# 8Port.net
KiCad netlist of a schematic drawn in Altium Designer
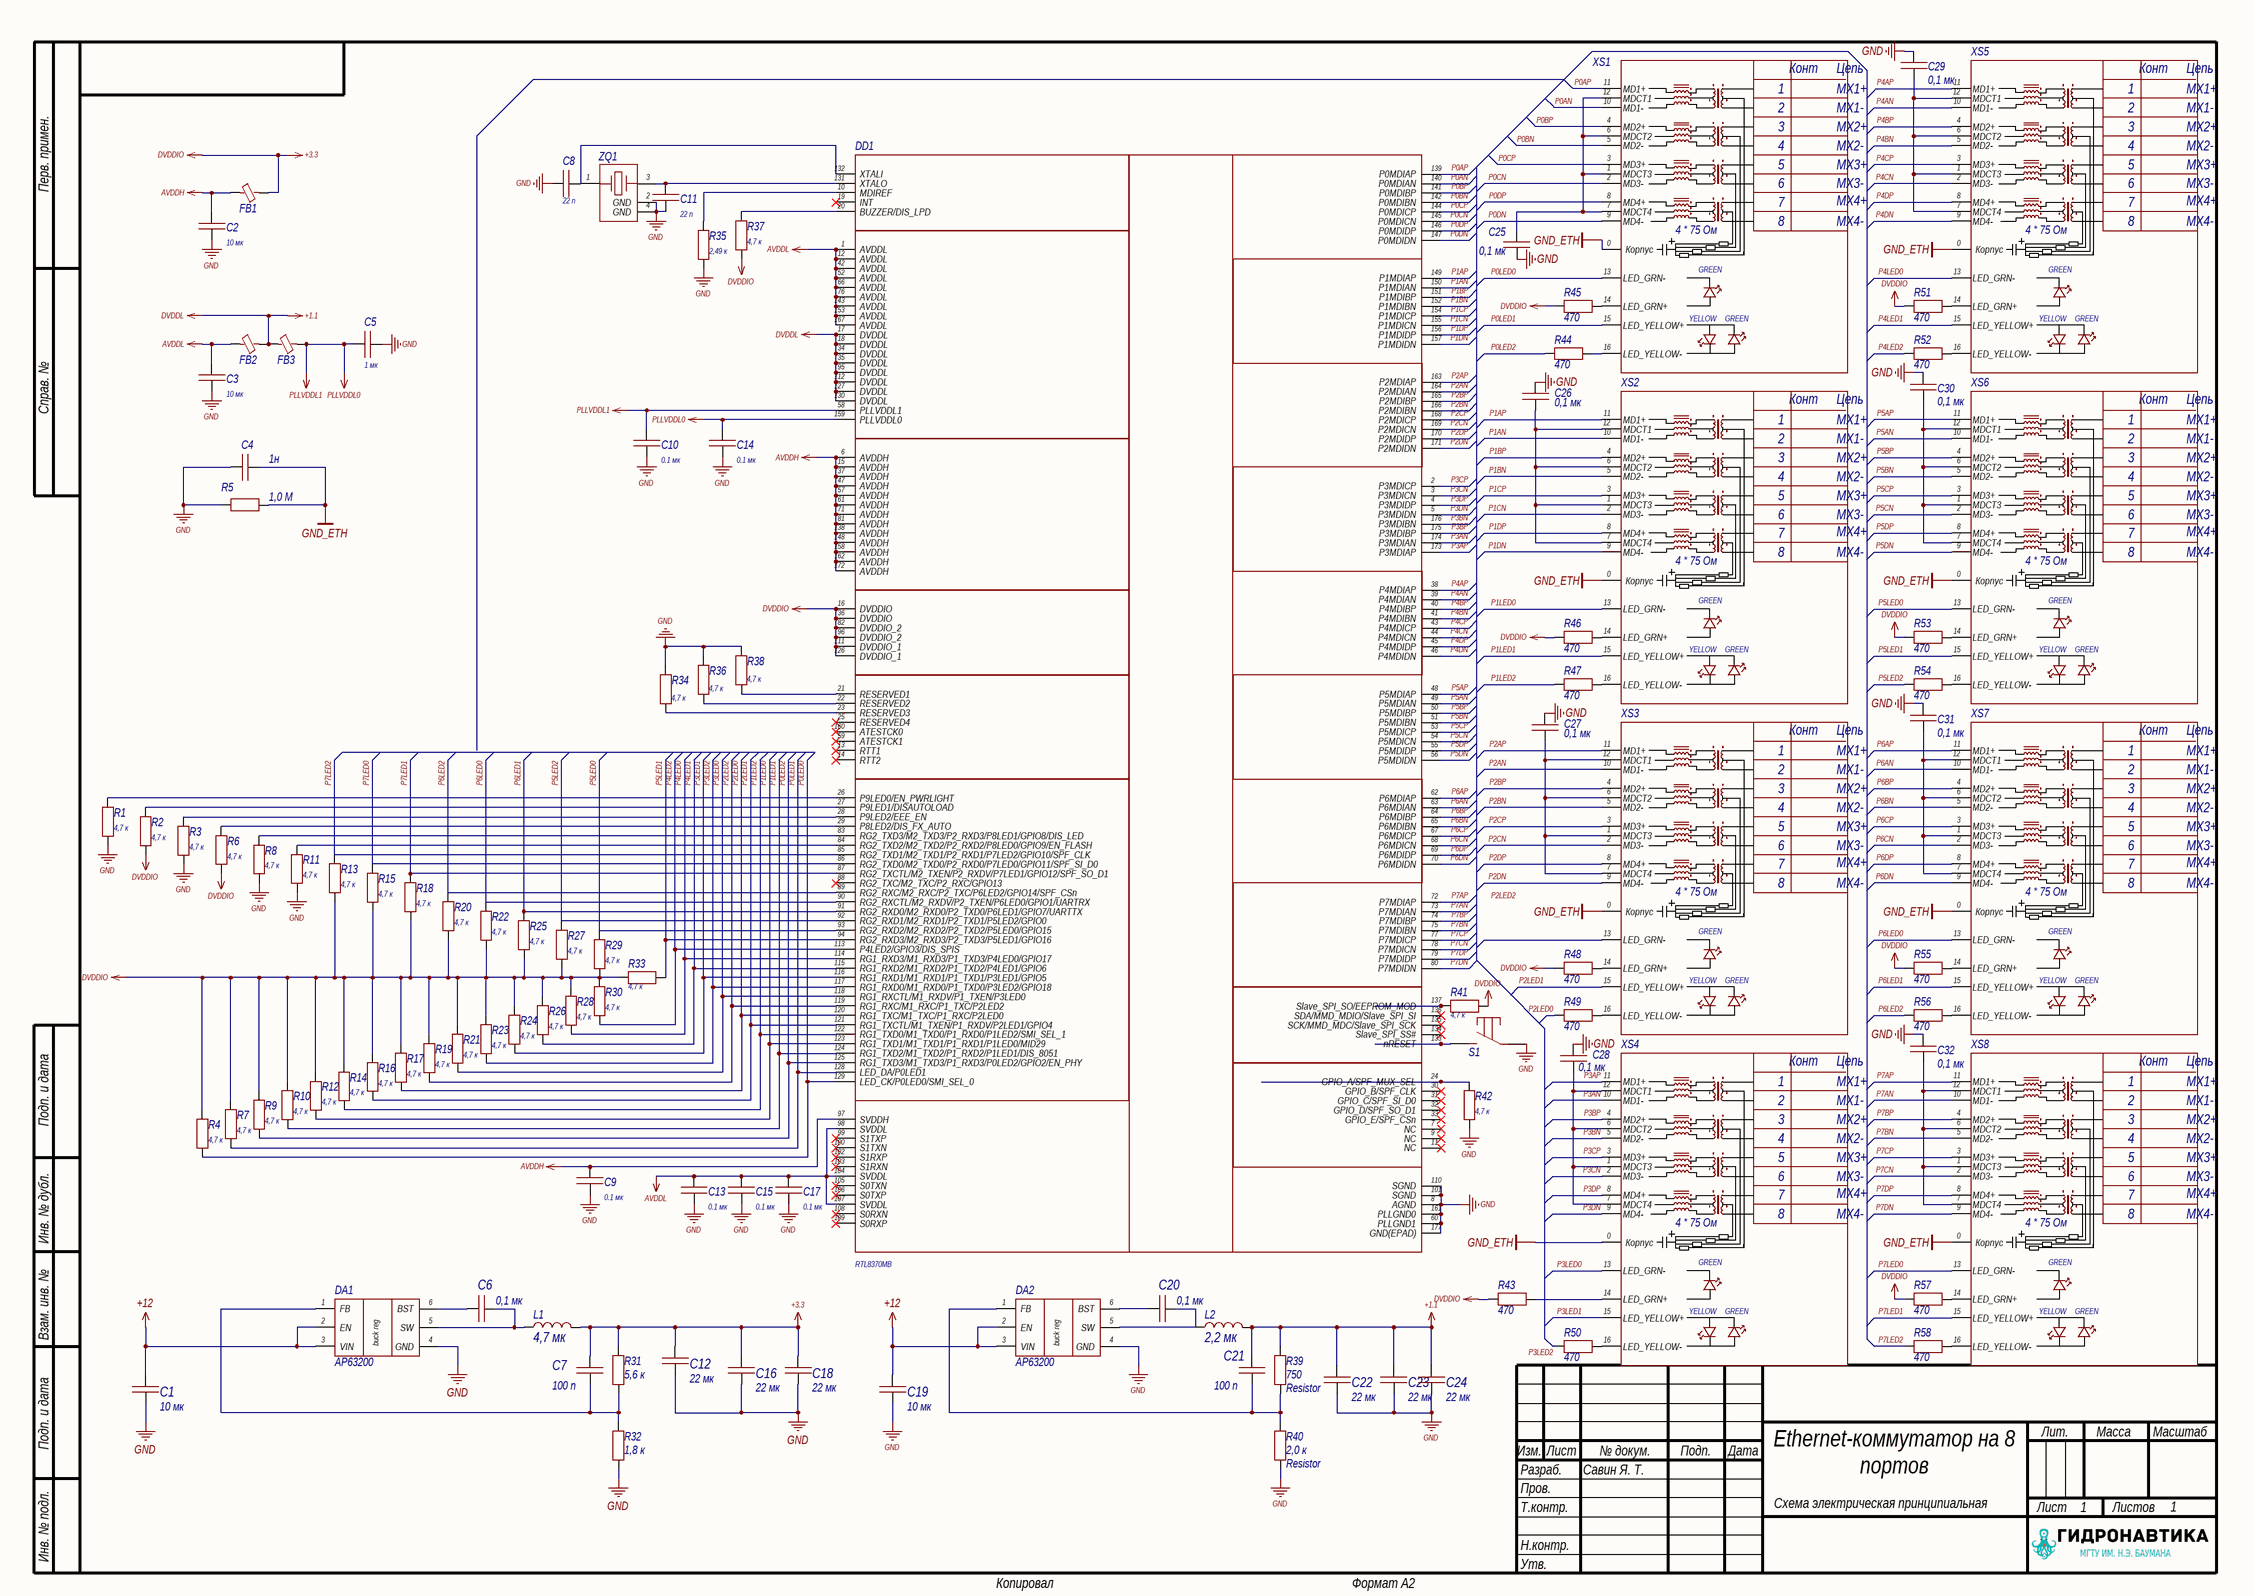
[diagram p0: 8Port.SchDoc]

(export (version "E")
  (design (tool "Eeschema 10.0.6"))
  (components
    (comp (ref "C1")
      (value "10 мк")
      (footprint "1210C")
      (description "Конденсатор 1210C ёмкостью 10 мк 10%, 35 В, X7R")
      (fields (field (name "PART NUMBER") "Capacitor_10u_10_35V_X7R_1210C") (field (name "TOLERANCE") "10%"))
      (libsource (lib "Hydrolib") (part "Capacitor"))
    )
    (comp (ref "C2")
      (value "10 мк")
      (footprint "0603C")
      (description "Конденсатор")
      (fields (field (name "PART NUMBER") "Capacitor"))
      (libsource (lib "Hydrolib") (part "Capacitor"))
    )
    (comp (ref "C3")
      (value "10 мк")
      (footprint "0603C")
      (description "Конденсатор")
      (fields (field (name "PART NUMBER") "Capacitor"))
      (libsource (lib "Hydrolib") (part "Capacitor"))
    )
    (comp (ref "C4")
      (value "1н")
      (footprint "1210C")
      (description "Конденсатор 1210C ёмкостью 1н 10%, 1000 В, X7R")
      (fields
        (field (name "PART NUMBER") "Capacitor_1n_10_1000V_X7R_1206C")
        (field (name "TOLERANCE") "10%")
        (field (name "АВТОР") "rreali")
      )
      (libsource (lib "Hydrolib") (part "Capacitor"))
    )
    (comp (ref "C5")
      (value "1 мк")
      (footprint "0603C")
      (description "Конденсатор")
      (fields (field (name "PART NUMBER") "Capacitor"))
      (libsource (lib "Hydrolib") (part "Capacitor"))
    )
    (comp (ref "C6")
      (value "0,1 мк")
      (footprint "0603C")
      (description "Конденсатор 0603C ёмкостью 0,1 мк 10%, 50 В, X7R")
      (fields (field (name "PART NUMBER") "Capacitor_0,1u_10_50V_X7R_0603C") (field (name "TOLERANCE") "10%"))
      (libsource (lib "Hydrolib") (part "Capacitor"))
    )
    (comp (ref "C7")
      (value "100 п")
      (footprint "0603C")
      (description "Конденсатор 0603C ёмкостью 100 п 10%, 50 В, X7R")
      (fields (field (name "PART NUMBER") "Capacitor_100p_10_50V_X7R_0603C") (field (name "TOLERANCE") "10%"))
      (libsource (lib "Hydrolib") (part "Capacitor"))
    )
    (comp (ref "C8")
      (value "22 п")
      (footprint "0603C")
      (description "Конденсатор")
      (fields (field (name "PART NUMBER") "Capacitor"))
      (libsource (lib "Hydrolib") (part "Capacitor"))
    )
    (comp (ref "C9")
      (value "0.1 мк")
      (footprint "0603C")
      (description "Конденсатор")
      (fields (field (name "PART NUMBER") "Capacitor"))
      (libsource (lib "Hydrolib") (part "Capacitor"))
    )
    (comp (ref "C10")
      (value "0.1 мк")
      (footprint "0603C")
      (description "Конденсатор")
      (fields (field (name "PART NUMBER") "Capacitor"))
      (libsource (lib "Hydrolib") (part "Capacitor"))
    )
    (comp (ref "C11")
      (value "22 п")
      (footprint "0603C")
      (description "Конденсатор")
      (fields (field (name "PART NUMBER") "Capacitor"))
      (libsource (lib "Hydrolib") (part "Capacitor"))
    )
    (comp (ref "C12")
      (value "22 мк")
      (footprint "1210C")
      (description "Конденсатор 1210C ёмкостью 22 мк 10%, 25 В, X7R")
      (fields (field (name "PART NUMBER") "Capacitor_22u_10_25V_X7R_1210C") (field (name "TOLERANCE") "10%"))
      (libsource (lib "Hydrolib") (part "Capacitor"))
    )
    (comp (ref "C13")
      (value "0.1 мк")
      (footprint "0603C")
      (description "Конденсатор")
      (fields (field (name "PART NUMBER") "Capacitor"))
      (libsource (lib "Hydrolib") (part "Capacitor"))
    )
    (comp (ref "C14")
      (value "0.1 мк")
      (footprint "0603C")
      (description "Конденсатор")
      (fields (field (name "PART NUMBER") "Capacitor"))
      (libsource (lib "Hydrolib") (part "Capacitor"))
    )
    (comp (ref "C15")
      (value "0.1 мк")
      (footprint "0603C")
      (description "Конденсатор")
      (fields (field (name "PART NUMBER") "Capacitor"))
      (libsource (lib "Hydrolib") (part "Capacitor"))
    )
    (comp (ref "C16")
      (value "22 мк")
      (footprint "1210C")
      (description "Конденсатор 1210C ёмкостью 22 мк 10%, 25 В, X7R")
      (fields (field (name "PART NUMBER") "Capacitor_22u_10_25V_X7R_1210C") (field (name "TOLERANCE") "10%"))
      (libsource (lib "Hydrolib") (part "Capacitor"))
    )
    (comp (ref "C17")
      (value "0.1 мк")
      (footprint "0603C")
      (description "Конденсатор")
      (fields (field (name "PART NUMBER") "Capacitor"))
      (libsource (lib "Hydrolib") (part "Capacitor"))
    )
    (comp (ref "C18")
      (value "22 мк")
      (footprint "1210C")
      (description "Конденсатор 1210C ёмкостью 22 мк 10%, 25 В, X7R")
      (fields (field (name "PART NUMBER") "Capacitor_22u_10_25V_X7R_1210C") (field (name "TOLERANCE") "10%"))
      (libsource (lib "Hydrolib") (part "Capacitor"))
    )
    (comp (ref "C19")
      (value "10 мк")
      (footprint "1210C")
      (description "Конденсатор 1210C ёмкостью 10 мк 10%, 35 В, X7R")
      (fields (field (name "PART NUMBER") "Capacitor_10u_10_35V_X7R_1210C") (field (name "TOLERANCE") "10%"))
      (libsource (lib "Hydrolib") (part "Capacitor"))
    )
    (comp (ref "C20")
      (value "0,1 мк")
      (footprint "0603C")
      (description "Конденсатор 0603C ёмкостью 0,1 мк 10%, 50 В, X7R")
      (fields (field (name "PART NUMBER") "Capacitor_0,1u_10_50V_X7R_0603C") (field (name "TOLERANCE") "10%"))
      (libsource (lib "Hydrolib") (part "Capacitor"))
    )
    (comp (ref "C21")
      (value "100 п")
      (footprint "0603C")
      (description "Конденсатор 0603C ёмкостью 100 п 10%, 50 В, X7R")
      (fields (field (name "PART NUMBER") "Capacitor_100p_10_50V_X7R_0603C") (field (name "TOLERANCE") "10%"))
      (libsource (lib "Hydrolib") (part "Capacitor"))
    )
    (comp (ref "C22")
      (value "22 мк")
      (footprint "1210C")
      (description "Конденсатор 1210C ёмкостью 22 мк 10%, 25 В, X7R")
      (fields (field (name "PART NUMBER") "Capacitor_22u_10_25V_X7R_1210C") (field (name "TOLERANCE") "10%"))
      (libsource (lib "Hydrolib") (part "Capacitor"))
    )
    (comp (ref "C23")
      (value "22 мк")
      (footprint "1210C")
      (description "Конденсатор 1210C ёмкостью 22 мк 10%, 25 В, X7R")
      (fields (field (name "PART NUMBER") "Capacitor_22u_10_25V_X7R_1210C") (field (name "TOLERANCE") "10%"))
      (libsource (lib "Hydrolib") (part "Capacitor"))
    )
    (comp (ref "C24")
      (value "22 мк")
      (footprint "1210C")
      (description "Конденсатор 1210C ёмкостью 22 мк 10%, 25 В, X7R")
      (fields (field (name "PART NUMBER") "Capacitor_22u_10_25V_X7R_1210C") (field (name "TOLERANCE") "10%"))
      (libsource (lib "Hydrolib") (part "Capacitor"))
    )
    (comp (ref "C25")
      (value "0,1 мк")
      (footprint "0603C")
      (description "Конденсатор 0603C ёмкостью 0,1 мк 10%, 50 В, X7R")
      (fields (field (name "PART NUMBER") "Capacitor_0,1u_10_50V_X7R_0603C") (field (name "TOLERANCE") "10%"))
      (libsource (lib "Hydrolib") (part "Capacitor"))
    )
    (comp (ref "C26")
      (value "0,1 мк")
      (footprint "0603C")
      (description "Конденсатор 0603C ёмкостью 0,1 мк 10%, 50 В, X7R")
      (fields (field (name "PART NUMBER") "Capacitor_0,1u_10_50V_X7R_0603C") (field (name "TOLERANCE") "10%"))
      (libsource (lib "Hydrolib") (part "Capacitor"))
    )
    (comp (ref "C27")
      (value "0,1 мк")
      (footprint "0603C")
      (description "Конденсатор 0603C ёмкостью 0,1 мк 10%, 50 В, X7R")
      (fields (field (name "PART NUMBER") "Capacitor_0,1u_10_50V_X7R_0603C") (field (name "TOLERANCE") "10%"))
      (libsource (lib "Hydrolib") (part "Capacitor"))
    )
    (comp (ref "C28")
      (value "0,1 мк")
      (footprint "0603C")
      (description "Конденсатор 0603C ёмкостью 0,1 мк 10%, 50 В, X7R")
      (fields (field (name "PART NUMBER") "Capacitor_0,1u_10_50V_X7R_0603C") (field (name "TOLERANCE") "10%"))
      (libsource (lib "Hydrolib") (part "Capacitor"))
    )
    (comp (ref "C29")
      (value "0,1 мк")
      (footprint "0603C")
      (description "Конденсатор 0603C ёмкостью 0,1 мк 10%, 50 В, X7R")
      (fields (field (name "PART NUMBER") "Capacitor_0,1u_10_50V_X7R_0603C") (field (name "TOLERANCE") "10%"))
      (libsource (lib "Hydrolib") (part "Capacitor"))
    )
    (comp (ref "C30")
      (value "0,1 мк")
      (footprint "0603C")
      (description "Конденсатор 0603C ёмкостью 0,1 мк 10%, 50 В, X7R")
      (fields (field (name "PART NUMBER") "Capacitor_0,1u_10_50V_X7R_0603C") (field (name "TOLERANCE") "10%"))
      (libsource (lib "Hydrolib") (part "Capacitor"))
    )
    (comp (ref "C31")
      (value "0,1 мк")
      (footprint "0603C")
      (description "Конденсатор 0603C ёмкостью 0,1 мк 10%, 50 В, X7R")
      (fields (field (name "PART NUMBER") "Capacitor_0,1u_10_50V_X7R_0603C") (field (name "TOLERANCE") "10%"))
      (libsource (lib "Hydrolib") (part "Capacitor"))
    )
    (comp (ref "C32")
      (value "0,1 мк")
      (footprint "0603C")
      (description "Конденсатор 0603C ёмкостью 0,1 мк 10%, 50 В, X7R")
      (fields (field (name "PART NUMBER") "Capacitor_0,1u_10_50V_X7R_0603C") (field (name "TOLERANCE") "10%"))
      (libsource (lib "Hydrolib") (part "Capacitor"))
    )
    (comp (ref "DA1")
      (value "AP63200")
      (footprint "TSOT26")
      (description "DC-DC понижающий преобразователь, Vin: 3.8 - 40 В, adj, 2 А")
      (libsource (lib "Hydrolib") (part "AP63200"))
    )
    (comp (ref "DA2")
      (value "AP63200")
      (footprint "TSOT26")
      (description "DC-DC понижающий преобразователь, Vin: 3.8 - 40 В, adj, 2 А")
      (libsource (lib "Hydrolib") (part "AP63200"))
    )
    (comp (ref "DD1")
      (value "RTL8370MB")
      (footprint "QFP40P2200X2200X120-177N:QFP40P2200X2200X120-177N")
      (libsource (lib "RTL8370MB") (part "RTL8370MB"))
    )
    (comp (ref "FB1")
      (value "BLM18AG102SN1D")
      (footprint "0603L")
      (description "Дроссель подавления ЭМП")
      (fields (field (name "АВТОР") "glebmih"))
      (libsource (lib "Hydrolib") (part "Ferrite_bead"))
    )
    (comp (ref "FB2")
      (value "BLM18AG102SN1D")
      (footprint "0603L")
      (description "Дроссель подавления ЭМП")
      (fields (field (name "АВТОР") "glebmih"))
      (libsource (lib "Hydrolib") (part "Ferrite_bead"))
    )
    (comp (ref "FB3")
      (value "BLM18AG102SN1D")
      (footprint "0603L")
      (description "Дроссель подавления ЭМП")
      (fields (field (name "АВТОР") "glebmih"))
      (libsource (lib "Hydrolib") (part "Ferrite_bead"))
    )
    (comp (ref "L1")
      (value "4,7 мк")
      (footprint "B82462G4")
      (description "Индуктивность на 4,7 мкГн, номинальный ток 2,5 А")
      (fields (field (name "PART NUMBER") "B82472G6472M") (field (name "АВТОР") "rreali"))
      (libsource (lib "Hydrolib") (part "Inductance"))
    )
    (comp (ref "L2")
      (value "2,2 мк")
      (footprint "CDRH6D12")
      (description "Индуктивность на 2,2 мкГн, номинальный ток 2,5 А")
      (fields (field (name "PART NUMBER") "CDRH6D12NP-2R2NC") (field (name "АВТОР") "rreali"))
      (libsource (lib "Hydrolib") (part "Inductance_1-3"))
    )
    (comp (ref "R1")
      (value "4,7 к")
      (footprint "0603R")
      (description "Резистор номиналом 4,7 кОм 1%")
      (fields (field (name "PART NUMBER") "Resistor_4.7k_1_0603") (field (name "TOLERANCE") "1%"))
      (libsource (lib "") (part "Resistor_1"))
    )
    (comp (ref "R2")
      (value "4,7 к")
      (footprint "0603R")
      (description "Резистор номиналом 4,7 кОм 1%")
      (fields (field (name "PART NUMBER") "Resistor_4.7k_1_0603") (field (name "TOLERANCE") "1%"))
      (libsource (lib "") (part "Resistor_1"))
    )
    (comp (ref "R3")
      (value "4,7 к")
      (footprint "0603R")
      (description "Резистор номиналом 4,7 кОм 1%")
      (fields (field (name "PART NUMBER") "Resistor_4.7k_1_0603") (field (name "TOLERANCE") "1%"))
      (libsource (lib "") (part "Resistor_1"))
    )
    (comp (ref "R4")
      (value "4,7 к")
      (footprint "0603R")
      (description "Резистор номиналом 4,7 кОм 1%")
      (fields (field (name "PART NUMBER") "Resistor_4.7k_1_0603") (field (name "TOLERANCE") "1%"))
      (libsource (lib "") (part "Resistor_1"))
    )
    (comp (ref "R5")
      (value "1,0 М")
      (footprint "0603R")
      (description "Резистор номиналом 1,0 МОм 1%")
      (fields (field (name "PART NUMBER") "Resistor_1.0M_1_0603") (field (name "TOLERANCE") "1%"))
      (libsource (lib "Hydrolib") (part "Resistor"))
    )
    (comp (ref "R6")
      (value "4,7 к")
      (footprint "0603R")
      (description "Резистор номиналом 4,7 кОм 1%")
      (fields (field (name "PART NUMBER") "Resistor_4.7k_1_0603") (field (name "TOLERANCE") "1%"))
      (libsource (lib "") (part "Resistor_1"))
    )
    (comp (ref "R7")
      (value "4,7 к")
      (footprint "0603R")
      (description "Резистор номиналом 4,7 кОм 1%")
      (fields (field (name "PART NUMBER") "Resistor_4.7k_1_0603") (field (name "TOLERANCE") "1%"))
      (libsource (lib "") (part "Resistor_1"))
    )
    (comp (ref "R8")
      (value "4,7 к")
      (footprint "0603R")
      (description "Резистор номиналом 4,7 кОм 1%")
      (fields (field (name "PART NUMBER") "Resistor_4.7k_1_0603") (field (name "TOLERANCE") "1%"))
      (libsource (lib "") (part "Resistor_1"))
    )
    (comp (ref "R9")
      (value "4,7 к")
      (footprint "0603R")
      (description "Резистор номиналом 4,7 кОм 1%")
      (fields (field (name "PART NUMBER") "Resistor_4.7k_1_0603") (field (name "TOLERANCE") "1%"))
      (libsource (lib "") (part "Resistor_1"))
    )
    (comp (ref "R10")
      (value "4,7 к")
      (footprint "0603R")
      (description "Резистор номиналом 4,7 кОм 1%")
      (fields (field (name "PART NUMBER") "Resistor_4.7k_1_0603") (field (name "TOLERANCE") "1%"))
      (libsource (lib "") (part "Resistor_1"))
    )
    (comp (ref "R11")
      (value "4,7 к")
      (footprint "0603R")
      (description "Резистор номиналом 4,7 кОм 1%")
      (fields (field (name "PART NUMBER") "Resistor_4.7k_1_0603") (field (name "TOLERANCE") "1%"))
      (libsource (lib "") (part "Resistor_1"))
    )
    (comp (ref "R12")
      (value "4,7 к")
      (footprint "0603R")
      (description "Резистор номиналом 4,7 кОм 1%")
      (fields (field (name "PART NUMBER") "Resistor_4.7k_1_0603") (field (name "TOLERANCE") "1%"))
      (libsource (lib "") (part "Resistor_1"))
    )
    (comp (ref "R13")
      (value "4,7 к")
      (footprint "0603R")
      (description "Резистор номиналом 4,7 кОм 1%")
      (fields (field (name "PART NUMBER") "Resistor_4.7k_1_0603") (field (name "TOLERANCE") "1%"))
      (libsource (lib "") (part "Resistor_1"))
    )
    (comp (ref "R14")
      (value "4,7 к")
      (footprint "0603R")
      (description "Резистор номиналом 4,7 кОм 1%")
      (fields (field (name "PART NUMBER") "Resistor_4.7k_1_0603") (field (name "TOLERANCE") "1%"))
      (libsource (lib "") (part "Resistor_1"))
    )
    (comp (ref "R15")
      (value "4,7 к")
      (footprint "0603R")
      (description "Резистор номиналом 4,7 кОм 1%")
      (fields (field (name "PART NUMBER") "Resistor_4.7k_1_0603") (field (name "TOLERANCE") "1%"))
      (libsource (lib "") (part "Resistor_1"))
    )
    (comp (ref "R16")
      (value "4,7 к")
      (footprint "0603R")
      (description "Резистор номиналом 4,7 кОм 1%")
      (fields (field (name "PART NUMBER") "Resistor_4.7k_1_0603") (field (name "TOLERANCE") "1%"))
      (libsource (lib "") (part "Resistor_1"))
    )
    (comp (ref "R17")
      (value "4,7 к")
      (footprint "0603R")
      (description "Резистор номиналом 4,7 кОм 1%")
      (fields (field (name "PART NUMBER") "Resistor_4.7k_1_0603") (field (name "TOLERANCE") "1%"))
      (libsource (lib "") (part "Resistor_1"))
    )
    (comp (ref "R18")
      (value "4,7 к")
      (footprint "0603R")
      (description "Резистор номиналом 4,7 кОм 1%")
      (fields (field (name "PART NUMBER") "Resistor_4.7k_1_0603") (field (name "TOLERANCE") "1%"))
      (libsource (lib "") (part "Resistor_1"))
    )
    (comp (ref "R19")
      (value "4,7 к")
      (footprint "0603R")
      (description "Резистор номиналом 4,7 кОм 1%")
      (fields (field (name "PART NUMBER") "Resistor_4.7k_1_0603") (field (name "TOLERANCE") "1%"))
      (libsource (lib "") (part "Resistor_1"))
    )
    (comp (ref "R20")
      (value "4,7 к")
      (footprint "0603R")
      (description "Резистор номиналом 4,7 кОм 1%")
      (fields (field (name "PART NUMBER") "Resistor_4.7k_1_0603") (field (name "TOLERANCE") "1%"))
      (libsource (lib "") (part "Resistor_1"))
    )
    (comp (ref "R21")
      (value "4,7 к")
      (footprint "0603R")
      (description "Резистор номиналом 4,7 кОм 1%")
      (fields (field (name "PART NUMBER") "Resistor_4.7k_1_0603") (field (name "TOLERANCE") "1%"))
      (libsource (lib "") (part "Resistor_1"))
    )
    (comp (ref "R22")
      (value "4,7 к")
      (footprint "0603R")
      (description "Резистор номиналом 4,7 кОм 1%")
      (fields (field (name "PART NUMBER") "Resistor_4.7k_1_0603") (field (name "TOLERANCE") "1%"))
      (libsource (lib "") (part "Resistor_1"))
    )
    (comp (ref "R23")
      (value "4,7 к")
      (footprint "0603R")
      (description "Резистор номиналом 4,7 кОм 1%")
      (fields (field (name "PART NUMBER") "Resistor_4.7k_1_0603") (field (name "TOLERANCE") "1%"))
      (libsource (lib "") (part "Resistor_1"))
    )
    (comp (ref "R24")
      (value "4,7 к")
      (footprint "0603R")
      (description "Резистор номиналом 4,7 кОм 1%")
      (fields (field (name "PART NUMBER") "Resistor_4.7k_1_0603") (field (name "TOLERANCE") "1%"))
      (libsource (lib "") (part "Resistor_1"))
    )
    (comp (ref "R25")
      (value "4,7 к")
      (footprint "0603R")
      (description "Резистор номиналом 4,7 кОм 1%")
      (fields (field (name "PART NUMBER") "Resistor_4.7k_1_0603") (field (name "TOLERANCE") "1%"))
      (libsource (lib "") (part "Resistor_1"))
    )
    (comp (ref "R26")
      (value "4,7 к")
      (footprint "0603R")
      (description "Резистор номиналом 4,7 кОм 1%")
      (fields (field (name "PART NUMBER") "Resistor_4.7k_1_0603") (field (name "TOLERANCE") "1%"))
      (libsource (lib "") (part "Resistor_1"))
    )
    (comp (ref "R27")
      (value "4,7 к")
      (footprint "0603R")
      (description "Резистор номиналом 4,7 кОм 1%")
      (fields (field (name "PART NUMBER") "Resistor_4.7k_1_0603") (field (name "TOLERANCE") "1%"))
      (libsource (lib "") (part "Resistor_1"))
    )
    (comp (ref "R28")
      (value "4,7 к")
      (footprint "0603R")
      (description "Резистор номиналом 4,7 кОм 1%")
      (fields (field (name "PART NUMBER") "Resistor_4.7k_1_0603") (field (name "TOLERANCE") "1%"))
      (libsource (lib "") (part "Resistor_1"))
    )
    (comp (ref "R29")
      (value "4,7 к")
      (footprint "0603R")
      (description "Резистор номиналом 4,7 кОм 1%")
      (fields (field (name "PART NUMBER") "Resistor_4.7k_1_0603") (field (name "TOLERANCE") "1%"))
      (libsource (lib "") (part "Resistor_1"))
    )
    (comp (ref "R30")
      (value "4,7 к")
      (footprint "0603R")
      (description "Резистор номиналом 4,7 кОм 1%")
      (fields (field (name "PART NUMBER") "Resistor_4.7k_1_0603") (field (name "TOLERANCE") "1%"))
      (libsource (lib "") (part "Resistor_1"))
    )
    (comp (ref "R31")
      (value "5,6 к")
      (footprint "0603R")
      (description "Резистор номиналом 5,6 кОм 1%")
      (fields (field (name "PART NUMBER") "Resistor_5.6k_1_0603") (field (name "TOLERANCE") "1%"))
      (libsource (lib "") (part "Resistor_2"))
    )
    (comp (ref "R32")
      (value "1,8 к")
      (footprint "0603R")
      (description "Резистор номиналом 1,8 кОм 1%")
      (fields (field (name "PART NUMBER") "Resistor_1.8k_1_0603") (field (name "TOLERANCE") "1%"))
      (libsource (lib "") (part "Resistor_2"))
    )
    (comp (ref "R33")
      (value "4,7 к")
      (footprint "0603R")
      (description "Резистор номиналом 4,7 кОм 1%")
      (fields (field (name "PART NUMBER") "Resistor_4.7k_1_0603") (field (name "TOLERANCE") "1%"))
      (libsource (lib "") (part "Resistor_3"))
    )
    (comp (ref "R34")
      (value "4,7 к")
      (footprint "0603R")
      (description "Резистор номиналом 4,7 кОм 1%")
      (fields (field (name "PART NUMBER") "Resistor_4.7k_1_0603") (field (name "TOLERANCE") "1%"))
      (libsource (lib "") (part "Resistor_2"))
    )
    (comp (ref "R35")
      (value "2,49 к")
      (footprint "0603R")
      (description "Резистор номиналом 4,7 кОм 1%")
      (fields (field (name "PART NUMBER") "Resistor_4.7k_1_0603") (field (name "TOLERANCE") "1%"))
      (libsource (lib "") (part "Resistor_2"))
    )
    (comp (ref "R36")
      (value "4,7 к")
      (footprint "0603R")
      (description "Резистор номиналом 4,7 кОм 1%")
      (fields (field (name "PART NUMBER") "Resistor_4.7k_1_0603") (field (name "TOLERANCE") "1%"))
      (libsource (lib "") (part "Resistor_2"))
    )
    (comp (ref "R37")
      (value "4,7 к")
      (footprint "0603R")
      (description "Резистор номиналом 4,7 кОм 1%")
      (fields (field (name "PART NUMBER") "Resistor_4.7k_1_0603") (field (name "TOLERANCE") "1%"))
      (libsource (lib "") (part "Resistor_2"))
    )
    (comp (ref "R38")
      (value "4,7 к")
      (footprint "0603R")
      (description "Резистор номиналом 4,7 кОм 1%")
      (fields (field (name "PART NUMBER") "Resistor_4.7k_1_0603") (field (name "TOLERANCE") "1%"))
      (libsource (lib "") (part "Resistor_2"))
    )
    (comp (ref "R39")
      (value "Resistor")
      (footprint "0603R")
      (description "Резистор номиналом 750 Ом 1%")
      (fields
        (field (name "ALTIUM_VALUE") "750")
        (field (name "PART NUMBER") "Resistor_750_1_0603")
        (field (name "TOLERANCE") "1%")
      )
      (libsource (lib "") (part "Resistor_2"))
    )
    (comp (ref "R40")
      (value "Resistor")
      (footprint "0603R")
      (description "Резистор номиналом 2,0 кОм 1%")
      (fields
        (field (name "ALTIUM_VALUE") "2,0 к")
        (field (name "PART NUMBER") "Resistor_2.0k_1_0603")
        (field (name "TOLERANCE") "1%")
      )
      (libsource (lib "") (part "Resistor_2"))
    )
    (comp (ref "R41")
      (value "4,7 к")
      (footprint "0603R")
      (description "Резистор номиналом 4,7 кОм 1%")
      (fields (field (name "PART NUMBER") "Resistor_4.7k_1_0603") (field (name "TOLERANCE") "1%"))
      (libsource (lib "Hydrolib") (part "Resistor"))
    )
    (comp (ref "R42")
      (value "4,7 к")
      (footprint "0603R")
      (description "Резистор номиналом 4,7 кОм 1%")
      (fields (field (name "PART NUMBER") "Resistor_4.7k_1_0603") (field (name "TOLERANCE") "1%"))
      (libsource (lib "") (part "Resistor_1"))
    )
    (comp (ref "R43")
      (value "470")
      (footprint "0603R")
      (description "Резистор номиналом 470 Ом 1%")
      (fields (field (name "PART NUMBER") "Resistor_470_1_0603") (field (name "TOLERANCE") "1%"))
      (libsource (lib "Hydrolib") (part "Resistor"))
    )
    (comp (ref "R44")
      (value "470")
      (footprint "0603R")
      (description "Резистор номиналом 470 Ом 1%")
      (fields (field (name "PART NUMBER") "Resistor_470_1_0603") (field (name "TOLERANCE") "1%"))
      (libsource (lib "Hydrolib") (part "Resistor"))
    )
    (comp (ref "R45")
      (value "470")
      (footprint "0603R")
      (description "Резистор номиналом 470 Ом 1%")
      (fields (field (name "PART NUMBER") "Resistor_470_1_0603") (field (name "TOLERANCE") "1%"))
      (libsource (lib "Hydrolib") (part "Resistor"))
    )
    (comp (ref "R46")
      (value "470")
      (footprint "0603R")
      (description "Резистор номиналом 470 Ом 1%")
      (fields (field (name "PART NUMBER") "Resistor_470_1_0603") (field (name "TOLERANCE") "1%"))
      (libsource (lib "Hydrolib") (part "Resistor"))
    )
    (comp (ref "R47")
      (value "470")
      (footprint "0603R")
      (description "Резистор номиналом 470 Ом 1%")
      (fields (field (name "PART NUMBER") "Resistor_470_1_0603") (field (name "TOLERANCE") "1%"))
      (libsource (lib "Hydrolib") (part "Resistor"))
    )
    (comp (ref "R48")
      (value "470")
      (footprint "0603R")
      (description "Резистор номиналом 470 Ом 1%")
      (fields (field (name "PART NUMBER") "Resistor_470_1_0603") (field (name "TOLERANCE") "1%"))
      (libsource (lib "Hydrolib") (part "Resistor"))
    )
    (comp (ref "R49")
      (value "470")
      (footprint "0603R")
      (description "Резистор номиналом 470 Ом 1%")
      (fields (field (name "PART NUMBER") "Resistor_470_1_0603") (field (name "TOLERANCE") "1%"))
      (libsource (lib "Hydrolib") (part "Resistor"))
    )
    (comp (ref "R50")
      (value "470")
      (footprint "0603R")
      (description "Резистор номиналом 470 Ом 1%")
      (fields (field (name "PART NUMBER") "Resistor_470_1_0603") (field (name "TOLERANCE") "1%"))
      (libsource (lib "Hydrolib") (part "Resistor"))
    )
    (comp (ref "R51")
      (value "470")
      (footprint "0603R")
      (description "Резистор номиналом 470 Ом 1%")
      (fields (field (name "PART NUMBER") "Resistor_470_1_0603") (field (name "TOLERANCE") "1%"))
      (libsource (lib "Hydrolib") (part "Resistor"))
    )
    (comp (ref "R52")
      (value "470")
      (footprint "0603R")
      (description "Резистор номиналом 470 Ом 1%")
      (fields (field (name "PART NUMBER") "Resistor_470_1_0603") (field (name "TOLERANCE") "1%"))
      (libsource (lib "Hydrolib") (part "Resistor"))
    )
    (comp (ref "R53")
      (value "470")
      (footprint "0603R")
      (description "Резистор номиналом 470 Ом 1%")
      (fields (field (name "PART NUMBER") "Resistor_470_1_0603") (field (name "TOLERANCE") "1%"))
      (libsource (lib "Hydrolib") (part "Resistor"))
    )
    (comp (ref "R54")
      (value "470")
      (footprint "0603R")
      (description "Резистор номиналом 470 Ом 1%")
      (fields (field (name "PART NUMBER") "Resistor_470_1_0603") (field (name "TOLERANCE") "1%"))
      (libsource (lib "Hydrolib") (part "Resistor"))
    )
    (comp (ref "R55")
      (value "470")
      (footprint "0603R")
      (description "Резистор номиналом 470 Ом 1%")
      (fields (field (name "PART NUMBER") "Resistor_470_1_0603") (field (name "TOLERANCE") "1%"))
      (libsource (lib "Hydrolib") (part "Resistor"))
    )
    (comp (ref "R56")
      (value "470")
      (footprint "0603R")
      (description "Резистор номиналом 470 Ом 1%")
      (fields (field (name "PART NUMBER") "Resistor_470_1_0603") (field (name "TOLERANCE") "1%"))
      (libsource (lib "Hydrolib") (part "Resistor"))
    )
    (comp (ref "R57")
      (value "470")
      (footprint "0603R")
      (description "Резистор номиналом 470 Ом 1%")
      (fields (field (name "PART NUMBER") "Resistor_470_1_0603") (field (name "TOLERANCE") "1%"))
      (libsource (lib "Hydrolib") (part "Resistor"))
    )
    (comp (ref "R58")
      (value "470")
      (footprint "0603R")
      (description "Резистор номиналом 470 Ом 1%")
      (fields (field (name "PART NUMBER") "Resistor_470_1_0603") (field (name "TOLERANCE") "1%"))
      (libsource (lib "Hydrolib") (part "Resistor"))
    )
    (comp (ref "S1")
      (value "Tact_button")
      (footprint "Button_SMD_6x6")
      (description "Тактовая кнопка")
      (libsource (lib "Hydrolib") (part "Tact_button"))
    )
    (comp (ref "XS1")
      (value "JK0-0136NL")
      (footprint "JK00136NL")
      (description "Модульный разъем (с трансформатором) Cat5/6, RJ45, Гнездо,  1 порт")
      (fields (field (name "MF") "Pulse Electronics") (field (name "АВТОР") "rreali"))
      (libsource (lib "Hydrolib") (part "JK0-0136NL"))
    )
    (comp (ref "XS2")
      (value "JK0-0136NL")
      (footprint "JK00136NL")
      (description "Модульный разъем (с трансформатором) Cat5/6, RJ45, Гнездо,  1 порт")
      (fields (field (name "MF") "Pulse Electronics") (field (name "АВТОР") "rreali"))
      (libsource (lib "Hydrolib") (part "JK0-0136NL"))
    )
    (comp (ref "XS3")
      (value "JK0-0136NL")
      (footprint "JK00136NL")
      (description "Модульный разъем (с трансформатором) Cat5/6, RJ45, Гнездо,  1 порт")
      (fields (field (name "MF") "Pulse Electronics") (field (name "АВТОР") "rreali"))
      (libsource (lib "Hydrolib") (part "JK0-0136NL"))
    )
    (comp (ref "XS4")
      (value "JK0-0136NL")
      (footprint "JK00136NL")
      (description "Модульный разъем (с трансформатором) Cat5/6, RJ45, Гнездо,  1 порт")
      (fields (field (name "MF") "Pulse Electronics") (field (name "АВТОР") "rreali"))
      (libsource (lib "Hydrolib") (part "JK0-0136NL"))
    )
    (comp (ref "XS5")
      (value "JK0-0136NL")
      (footprint "JK00136NL")
      (description "Модульный разъем (с трансформатором) Cat5/6, RJ45, Гнездо,  1 порт")
      (fields (field (name "MF") "Pulse Electronics") (field (name "АВТОР") "rreali"))
      (libsource (lib "Hydrolib") (part "JK0-0136NL"))
    )
    (comp (ref "XS6")
      (value "JK0-0136NL")
      (footprint "JK00136NL")
      (description "Модульный разъем (с трансформатором) Cat5/6, RJ45, Гнездо,  1 порт")
      (fields (field (name "MF") "Pulse Electronics") (field (name "АВТОР") "rreali"))
      (libsource (lib "Hydrolib") (part "JK0-0136NL"))
    )
    (comp (ref "XS7")
      (value "JK0-0136NL")
      (footprint "JK00136NL")
      (description "Модульный разъем (с трансформатором) Cat5/6, RJ45, Гнездо,  1 порт")
      (fields (field (name "MF") "Pulse Electronics") (field (name "АВТОР") "rreali"))
      (libsource (lib "Hydrolib") (part "JK0-0136NL"))
    )
    (comp (ref "XS8")
      (value "JK0-0136NL")
      (footprint "JK00136NL")
      (description "Модульный разъем (с трансформатором) Cat5/6, RJ45, Гнездо,  1 порт")
      (fields (field (name "MF") "Pulse Electronics") (field (name "АВТОР") "rreali"))
      (libsource (lib "Hydrolib") (part "JK0-0136NL"))
    )
    (comp (ref "ZQ1")
      (value "X322525MOB4SI")
      (footprint "X322525MOB4SI")
      (description "Кварцевый резонатор SMD 25 МГц ±10ppm SMD-3225_4P")
      (fields (field (name "АВТОР") "rreali"))
      (libsource (lib "Hydrolib") (part "XTAL_1-3_GND"))
    )
  )
  (nets
    (net (code "1") (name "+1.1") (class "Default")
      (node (ref "C21") (pin "2") (pinfunction "2_2") (pintype "passive"))
      (node (ref "C22") (pin "2") (pinfunction "2_2") (pintype "passive"))
      (node (ref "C23") (pin "2") (pinfunction "2_2") (pintype "passive"))
      (node (ref "C24") (pin "2") (pinfunction "2_2") (pintype "passive"))
      (node (ref "DD1") (pin "112") (pinfunction "DVDDL_112") (pintype "passive"))
      (node (ref "DD1") (pin "127") (pinfunction "DVDDL_127") (pintype "passive"))
      (node (ref "DD1") (pin "130") (pinfunction "DVDDL_130") (pintype "passive"))
      (node (ref "DD1") (pin "17") (pinfunction "DVDDL_17") (pintype "passive"))
      (node (ref "DD1") (pin "18") (pinfunction "DVDDL_18") (pintype "passive"))
      (node (ref "DD1") (pin "34") (pinfunction "DVDDL_34") (pintype "passive"))
      (node (ref "DD1") (pin "35") (pinfunction "DVDDL_35") (pintype "passive"))
      (node (ref "DD1") (pin "95") (pinfunction "DVDDL_95") (pintype "passive"))
      (node (ref "FB2") (pin "2") (pinfunction "2_2") (pintype "passive"))
      (node (ref "FB3") (pin "1") (pinfunction "1_1") (pintype "passive"))
      (node (ref "L2") (pin "3") (pinfunction "3_3") (pintype "passive"))
      (node (ref "R39") (pin "2") (pinfunction "2_2") (pintype "passive"))
    )
    (net (code "2") (name "+3.3") (class "Default")
      (node (ref "C12") (pin "2") (pinfunction "2_2") (pintype "passive"))
      (node (ref "C16") (pin "2") (pinfunction "2_2") (pintype "passive"))
      (node (ref "C18") (pin "2") (pinfunction "2_2") (pintype "passive"))
      (node (ref "C7") (pin "2") (pinfunction "2_2") (pintype "passive"))
      (node (ref "DD1") (pin "111") (pinfunction "DVDDIO_1_111") (pintype "passive"))
      (node (ref "DD1") (pin "126") (pinfunction "DVDDIO_1_126") (pintype "passive"))
      (node (ref "DD1") (pin "16") (pinfunction "DVDDIO_16") (pintype "passive"))
      (node (ref "DD1") (pin "36") (pinfunction "DVDDIO_36") (pintype "passive"))
      (node (ref "DD1") (pin "82") (pinfunction "DVDDIO_2_82") (pintype "passive"))
      (node (ref "DD1") (pin "96") (pinfunction "DVDDIO_2_96") (pintype "passive"))
      (node (ref "FB1") (pin "2") (pinfunction "2_2") (pintype "passive"))
      (node (ref "L1") (pin "2") (pinfunction "2_2") (pintype "passive"))
      (node (ref "R10") (pin "1") (pinfunction "1_1") (pintype "passive"))
      (node (ref "R12") (pin "1") (pinfunction "1_1") (pintype "passive"))
      (node (ref "R13") (pin "2") (pinfunction "2_2") (pintype "passive"))
      (node (ref "R14") (pin "1") (pinfunction "1_1") (pintype "passive"))
      (node (ref "R15") (pin "2") (pinfunction "2_2") (pintype "passive"))
      (node (ref "R16") (pin "1") (pinfunction "1_1") (pintype "passive"))
      (node (ref "R17") (pin "1") (pinfunction "1_1") (pintype "passive"))
      (node (ref "R18") (pin "2") (pinfunction "2_2") (pintype "passive"))
      (node (ref "R19") (pin "1") (pinfunction "1_1") (pintype "passive"))
      (node (ref "R2") (pin "2") (pinfunction "2_2") (pintype "passive"))
      (node (ref "R20") (pin "2") (pinfunction "2_2") (pintype "passive"))
      (node (ref "R21") (pin "1") (pinfunction "1_1") (pintype "passive"))
      (node (ref "R22") (pin "2") (pinfunction "2_2") (pintype "passive"))
      (node (ref "R23") (pin "1") (pinfunction "1_1") (pintype "passive"))
      (node (ref "R24") (pin "1") (pinfunction "1_1") (pintype "passive"))
      (node (ref "R25") (pin "2") (pinfunction "2_2") (pintype "passive"))
      (node (ref "R26") (pin "1") (pinfunction "1_1") (pintype "passive"))
      (node (ref "R27") (pin "2") (pinfunction "2_2") (pintype "passive"))
      (node (ref "R28") (pin "1") (pinfunction "1_1") (pintype "passive"))
      (node (ref "R29") (pin "2") (pinfunction "2_2") (pintype "passive"))
      (node (ref "R30") (pin "1") (pinfunction "1_1") (pintype "passive"))
      (node (ref "R31") (pin "2") (pinfunction "2_2") (pintype "passive"))
      (node (ref "R33") (pin "2") (pinfunction "2_2") (pintype "passive"))
      (node (ref "R37") (pin "1") (pinfunction "1_1") (pintype "passive"))
      (node (ref "R4") (pin "1") (pinfunction "1_1") (pintype "passive"))
      (node (ref "R41") (pin "2") (pinfunction "2_2") (pintype "passive"))
      (node (ref "R43") (pin "1") (pinfunction "1_1") (pintype "passive"))
      (node (ref "R45") (pin "1") (pinfunction "1_1") (pintype "passive"))
      (node (ref "R46") (pin "1") (pinfunction "1_1") (pintype "passive"))
      (node (ref "R48") (pin "1") (pinfunction "1_1") (pintype "passive"))
      (node (ref "R51") (pin "1") (pinfunction "1_1") (pintype "passive"))
      (node (ref "R53") (pin "1") (pinfunction "1_1") (pintype "passive"))
      (node (ref "R55") (pin "1") (pinfunction "1_1") (pintype "passive"))
      (node (ref "R57") (pin "1") (pinfunction "1_1") (pintype "passive"))
      (node (ref "R6") (pin "2") (pinfunction "2_2") (pintype "passive"))
      (node (ref "R7") (pin "1") (pinfunction "1_1") (pintype "passive"))
      (node (ref "R9") (pin "1") (pinfunction "1_1") (pintype "passive"))
    )
    (net (code "3") (name "+12") (class "Default")
      (node (ref "C1") (pin "2") (pinfunction "2_2") (pintype "passive"))
      (node (ref "C19") (pin "2") (pinfunction "2_2") (pintype "passive"))
      (node (ref "DA1") (pin "2") (pinfunction "EN_2") (pintype "passive"))
      (node (ref "DA1") (pin "3") (pinfunction "VIN_3") (pintype "passive"))
      (node (ref "DA2") (pin "2") (pinfunction "EN_2") (pintype "passive"))
      (node (ref "DA2") (pin "3") (pinfunction "VIN_3") (pintype "passive"))
    )
    (net (code "4") (name "/P0AN") (class "Default")
      (node (ref "DD1") (pin "140") (pinfunction "P0MDIAN_140") (pintype "passive"))
      (node (ref "XS1") (pin "10") (pinfunction "MD1-_10") (pintype "passive"))
    )
    (net (code "5") (name "/P0AP") (class "Default")
      (node (ref "DD1") (pin "139") (pinfunction "P0MDIAP_139") (pintype "passive"))
      (node (ref "XS1") (pin "11") (pinfunction "MD1+_11") (pintype "passive"))
    )
    (net (code "6") (name "/P0BN") (class "Default")
      (node (ref "DD1") (pin "142") (pinfunction "P0MDIBN_142") (pintype "passive"))
      (node (ref "XS1") (pin "5") (pinfunction "MD2-_5") (pintype "passive"))
    )
    (net (code "7") (name "/P0BP") (class "Default")
      (node (ref "DD1") (pin "141") (pinfunction "P0MDIBP_141") (pintype "passive"))
      (node (ref "XS1") (pin "4") (pinfunction "MD2+_4") (pintype "passive"))
    )
    (net (code "8") (name "/P0CN") (class "Default")
      (node (ref "DD1") (pin "145") (pinfunction "P0MDICN_145") (pintype "passive"))
      (node (ref "XS1") (pin "2") (pinfunction "MD3-_2") (pintype "passive"))
    )
    (net (code "9") (name "/P0CP") (class "Default")
      (node (ref "DD1") (pin "144") (pinfunction "P0MDICP_144") (pintype "passive"))
      (node (ref "XS1") (pin "3") (pinfunction "MD3+_3") (pintype "passive"))
    )
    (net (code "10") (name "/P0DN") (class "Default")
      (node (ref "DD1") (pin "147") (pinfunction "P0MDIDN_147") (pintype "passive"))
      (node (ref "XS1") (pin "9") (pinfunction "MD4-_9") (pintype "passive"))
    )
    (net (code "11") (name "/P0DP") (class "Default")
      (node (ref "DD1") (pin "146") (pinfunction "P0MDIDP_146") (pintype "passive"))
      (node (ref "XS1") (pin "8") (pinfunction "MD4+_8") (pintype "passive"))
    )
    (net (code "12") (name "/P0LED0") (class "Default")
      (node (ref "DD1") (pin "129") (pinfunction "LED_CK/P0LED0/SMI_SEL_0_129") (pintype "passive"))
      (node (ref "R4") (pin "2") (pinfunction "2_2") (pintype "passive"))
      (node (ref "XS1") (pin "13") (pinfunction "LED_GRN-_13") (pintype "passive"))
    )
    (net (code "13") (name "/P0LED1") (class "Default")
      (node (ref "DD1") (pin "128") (pinfunction "LED_DA/P0LED1_128") (pintype "passive"))
      (node (ref "R7") (pin "2") (pinfunction "2_2") (pintype "passive"))
      (node (ref "XS1") (pin "15") (pinfunction "LED_YELLOW+_15") (pintype "passive"))
    )
    (net (code "14") (name "/P0LED2") (class "Default")
      (node (ref "DD1") (pin "125") (pinfunction "RG1_TXD3/M1_TXD3/P1_RXD3/P0LED2/GPIO2/EN_PHY_125") (pintype "passive"))
      (node (ref "R44") (pin "1") (pinfunction "1_1") (pintype "passive"))
      (node (ref "R9") (pin "2") (pinfunction "2_2") (pintype "passive"))
    )
    (net (code "15") (name "/P1AN") (class "Default")
      (node (ref "DD1") (pin "150") (pinfunction "P1MDIAN_150") (pintype "passive"))
      (node (ref "XS2") (pin "10") (pinfunction "MD1-_10") (pintype "passive"))
    )
    (net (code "16") (name "/P1AP") (class "Default")
      (node (ref "DD1") (pin "149") (pinfunction "P1MDIAP_149") (pintype "passive"))
      (node (ref "XS2") (pin "11") (pinfunction "MD1+_11") (pintype "passive"))
    )
    (net (code "17") (name "/P1BN") (class "Default")
      (node (ref "DD1") (pin "152") (pinfunction "P1MDIBN_152") (pintype "passive"))
      (node (ref "XS2") (pin "5") (pinfunction "MD2-_5") (pintype "passive"))
    )
    (net (code "18") (name "/P1BP") (class "Default")
      (node (ref "DD1") (pin "151") (pinfunction "P1MDIBP_151") (pintype "passive"))
      (node (ref "XS2") (pin "4") (pinfunction "MD2+_4") (pintype "passive"))
    )
    (net (code "19") (name "/P1CN") (class "Default")
      (node (ref "DD1") (pin "155") (pinfunction "P1MDICN_155") (pintype "passive"))
      (node (ref "XS2") (pin "2") (pinfunction "MD3-_2") (pintype "passive"))
    )
    (net (code "20") (name "/P1CP") (class "Default")
      (node (ref "DD1") (pin "154") (pinfunction "P1MDICP_154") (pintype "passive"))
      (node (ref "XS2") (pin "3") (pinfunction "MD3+_3") (pintype "passive"))
    )
    (net (code "21") (name "/P1DN") (class "Default")
      (node (ref "DD1") (pin "157") (pinfunction "P1MDIDN_157") (pintype "passive"))
      (node (ref "XS2") (pin "9") (pinfunction "MD4-_9") (pintype "passive"))
    )
    (net (code "22") (name "/P1DP") (class "Default")
      (node (ref "DD1") (pin "156") (pinfunction "P1MDIDP_156") (pintype "passive"))
      (node (ref "XS2") (pin "8") (pinfunction "MD4+_8") (pintype "passive"))
    )
    (net (code "23") (name "/P1LED0") (class "Default")
      (node (ref "DD1") (pin "123") (pinfunction "RG1_TXD1/M1_TXD1/P1_RXD1/P1LED0/MID29_123") (pintype "passive"))
      (node (ref "R12") (pin "2") (pinfunction "2_2") (pintype "passive"))
      (node (ref "XS2") (pin "13") (pinfunction "LED_GRN-_13") (pintype "passive"))
    )
    (net (code "24") (name "/P1LED1") (class "Default")
      (node (ref "DD1") (pin "124") (pinfunction "RG1_TXD2/M1_TXD2/P1_RXD2/P1LED1/DIS_8051_124") (pintype "passive"))
      (node (ref "R10") (pin "2") (pinfunction "2_2") (pintype "passive"))
      (node (ref "XS2") (pin "15") (pinfunction "LED_YELLOW+_15") (pintype "passive"))
    )
    (net (code "25") (name "/P1LED2") (class "Default")
      (node (ref "DD1") (pin "122") (pinfunction "RG1_TXD0/M1_TXD0/P1_RXD0/P1LED2/SMI_SEL_1_122") (pintype "passive"))
      (node (ref "R14") (pin "2") (pinfunction "2_2") (pintype "passive"))
      (node (ref "R47") (pin "1") (pinfunction "1_1") (pintype "passive"))
    )
    (net (code "26") (name "/P2AN") (class "Default")
      (node (ref "DD1") (pin "164") (pinfunction "P2MDIAN_164") (pintype "passive"))
      (node (ref "XS3") (pin "10") (pinfunction "MD1-_10") (pintype "passive"))
    )
    (net (code "27") (name "/P2AP") (class "Default")
      (node (ref "DD1") (pin "163") (pinfunction "P2MDIAP_163") (pintype "passive"))
      (node (ref "XS3") (pin "11") (pinfunction "MD1+_11") (pintype "passive"))
    )
    (net (code "28") (name "/P2BN") (class "Default")
      (node (ref "DD1") (pin "166") (pinfunction "P2MDIBN_166") (pintype "passive"))
      (node (ref "XS3") (pin "5") (pinfunction "MD2-_5") (pintype "passive"))
    )
    (net (code "29") (name "/P2BP") (class "Default")
      (node (ref "DD1") (pin "165") (pinfunction "P2MDIBP_165") (pintype "passive"))
      (node (ref "XS3") (pin "4") (pinfunction "MD2+_4") (pintype "passive"))
    )
    (net (code "30") (name "/P2CN") (class "Default")
      (node (ref "DD1") (pin "169") (pinfunction "P2MDICN_169") (pintype "passive"))
      (node (ref "XS3") (pin "2") (pinfunction "MD3-_2") (pintype "passive"))
    )
    (net (code "31") (name "/P2CP") (class "Default")
      (node (ref "DD1") (pin "168") (pinfunction "P2MDICP_168") (pintype "passive"))
      (node (ref "XS3") (pin "3") (pinfunction "MD3+_3") (pintype "passive"))
    )
    (net (code "32") (name "/P2DN") (class "Default")
      (node (ref "DD1") (pin "171") (pinfunction "P2MDIDN_171") (pintype "passive"))
      (node (ref "XS3") (pin "9") (pinfunction "MD4-_9") (pintype "passive"))
    )
    (net (code "33") (name "/P2DP") (class "Default")
      (node (ref "DD1") (pin "170") (pinfunction "P2MDIDP_170") (pintype "passive"))
      (node (ref "XS3") (pin "8") (pinfunction "MD4+_8") (pintype "passive"))
    )
    (net (code "34") (name "/P2LED0") (class "Default")
      (node (ref "DD1") (pin "120") (pinfunction "RG1_TXC/M1_TXC/P1_RXC/P2LED0_120") (pintype "passive"))
      (node (ref "R17") (pin "2") (pinfunction "2_2") (pintype "passive"))
      (node (ref "R49") (pin "1") (pinfunction "1_1") (pintype "passive"))
    )
    (net (code "35") (name "/P2LED1") (class "Default")
      (node (ref "DD1") (pin "121") (pinfunction "RG1_TXCTL/M1_TXEN/P1_RXDV/P2LED1/GPIO4_121") (pintype "passive"))
      (node (ref "R16") (pin "2") (pinfunction "2_2") (pintype "passive"))
      (node (ref "XS3") (pin "15") (pinfunction "LED_YELLOW+_15") (pintype "passive"))
    )
    (net (code "36") (name "/P2LED2") (class "Default")
      (node (ref "DD1") (pin "119") (pinfunction "RG1_RXC/M1_RXC/P1_TXC/P2LED2_119") (pintype "passive"))
      (node (ref "R19") (pin "2") (pinfunction "2_2") (pintype "passive"))
    )
    (net (code "37") (name "/P3AN") (class "Default")
      (node (ref "DD1") (pin "174") (pinfunction "P3MDIAN_174") (pintype "passive"))
      (node (ref "XS4") (pin "10") (pinfunction "MD1-_10") (pintype "passive"))
    )
    (net (code "38") (name "/P3AP") (class "Default")
      (node (ref "DD1") (pin "173") (pinfunction "P3MDIAP_173") (pintype "passive"))
      (node (ref "XS4") (pin "11") (pinfunction "MD1+_11") (pintype "passive"))
    )
    (net (code "39") (name "/P3BN") (class "Default")
      (node (ref "DD1") (pin "176") (pinfunction "P3MDIBN_176") (pintype "passive"))
      (node (ref "XS4") (pin "5") (pinfunction "MD2-_5") (pintype "passive"))
    )
    (net (code "40") (name "/P3BP") (class "Default")
      (node (ref "DD1") (pin "175") (pinfunction "P3MDIBP_175") (pintype "passive"))
      (node (ref "XS4") (pin "4") (pinfunction "MD2+_4") (pintype "passive"))
    )
    (net (code "41") (name "/P3CN") (class "Default")
      (node (ref "DD1") (pin "3") (pinfunction "P3MDICN_3") (pintype "passive"))
      (node (ref "XS4") (pin "2") (pinfunction "MD3-_2") (pintype "passive"))
    )
    (net (code "42") (name "/P3CP") (class "Default")
      (node (ref "DD1") (pin "2") (pinfunction "P3MDICP_2") (pintype "passive"))
      (node (ref "XS4") (pin "3") (pinfunction "MD3+_3") (pintype "passive"))
    )
    (net (code "43") (name "/P3DN") (class "Default")
      (node (ref "DD1") (pin "5") (pinfunction "P3MDIDN_5") (pintype "passive"))
      (node (ref "XS4") (pin "9") (pinfunction "MD4-_9") (pintype "passive"))
    )
    (net (code "44") (name "/P3DP") (class "Default")
      (node (ref "DD1") (pin "4") (pinfunction "P3MDIDP_4") (pintype "passive"))
      (node (ref "XS4") (pin "8") (pinfunction "MD4+_8") (pintype "passive"))
    )
    (net (code "45") (name "/P3LED0") (class "Default")
      (node (ref "DD1") (pin "118") (pinfunction "RG1_RXCTL/M1_RXDV/P1_TXEN/P3LED0_118") (pintype "passive"))
      (node (ref "R21") (pin "2") (pinfunction "2_2") (pintype "passive"))
      (node (ref "XS4") (pin "13") (pinfunction "LED_GRN-_13") (pintype "passive"))
    )
    (net (code "46") (name "/P3LED1") (class "Default")
      (node (ref "DD1") (pin "116") (pinfunction "RG1_RXD1/M1_RXD1/P1_TXD1/P3LED1/GPIO5_116") (pintype "passive"))
      (node (ref "R24") (pin "2") (pinfunction "2_2") (pintype "passive"))
      (node (ref "XS4") (pin "15") (pinfunction "LED_YELLOW+_15") (pintype "passive"))
    )
    (net (code "47") (name "/P3LED2") (class "Default")
      (node (ref "DD1") (pin "117") (pinfunction "RG1_RXD0/M1_RXD0/P1_TXD0/P3LED2/GPIO18_117") (pintype "passive"))
      (node (ref "R23") (pin "2") (pinfunction "2_2") (pintype "passive"))
      (node (ref "R50") (pin "1") (pinfunction "1_1") (pintype "passive"))
    )
    (net (code "48") (name "/P4AN") (class "Default")
      (node (ref "DD1") (pin "39") (pinfunction "P4MDIAN_39") (pintype "passive"))
      (node (ref "XS5") (pin "10") (pinfunction "MD1-_10") (pintype "passive"))
    )
    (net (code "49") (name "/P4AP") (class "Default")
      (node (ref "DD1") (pin "38") (pinfunction "P4MDIAP_38") (pintype "passive"))
      (node (ref "XS5") (pin "11") (pinfunction "MD1+_11") (pintype "passive"))
    )
    (net (code "50") (name "/P4BN") (class "Default")
      (node (ref "DD1") (pin "41") (pinfunction "P4MDIBN_41") (pintype "passive"))
      (node (ref "XS5") (pin "5") (pinfunction "MD2-_5") (pintype "passive"))
    )
    (net (code "51") (name "/P4BP") (class "Default")
      (node (ref "DD1") (pin "40") (pinfunction "P4MDIBP_40") (pintype "passive"))
      (node (ref "XS5") (pin "4") (pinfunction "MD2+_4") (pintype "passive"))
    )
    (net (code "52") (name "/P4CN") (class "Default")
      (node (ref "DD1") (pin "44") (pinfunction "P4MDICN_44") (pintype "passive"))
      (node (ref "XS5") (pin "2") (pinfunction "MD3-_2") (pintype "passive"))
    )
    (net (code "53") (name "/P4CP") (class "Default")
      (node (ref "DD1") (pin "43") (pinfunction "P4MDICP_43") (pintype "passive"))
      (node (ref "XS5") (pin "3") (pinfunction "MD3+_3") (pintype "passive"))
    )
    (net (code "54") (name "/P4DN") (class "Default")
      (node (ref "DD1") (pin "46") (pinfunction "P4MDIDN_46") (pintype "passive"))
      (node (ref "XS5") (pin "9") (pinfunction "MD4-_9") (pintype "passive"))
    )
    (net (code "55") (name "/P4DP") (class "Default")
      (node (ref "DD1") (pin "45") (pinfunction "P4MDIDP_45") (pintype "passive"))
      (node (ref "XS5") (pin "8") (pinfunction "MD4+_8") (pintype "passive"))
    )
    (net (code "56") (name "/P4LED0") (class "Default")
      (node (ref "DD1") (pin "114") (pinfunction "RG1_RXD3/M1_RXD3/P1_TXD3/P4LED0/GPIO17_114") (pintype "passive"))
      (node (ref "R28") (pin "2") (pinfunction "2_2") (pintype "passive"))
      (node (ref "XS5") (pin "13") (pinfunction "LED_GRN-_13") (pintype "passive"))
    )
    (net (code "57") (name "/P4LED1") (class "Default")
      (node (ref "DD1") (pin "115") (pinfunction "RG1_RXD2/M1_RXD2/P1_TXD2/P4LED1/GPIO6_115") (pintype "passive"))
      (node (ref "R26") (pin "2") (pinfunction "2_2") (pintype "passive"))
      (node (ref "XS5") (pin "15") (pinfunction "LED_YELLOW+_15") (pintype "passive"))
    )
    (net (code "58") (name "/P4LED2") (class "Default")
      (node (ref "DD1") (pin "113") (pinfunction "P4LED2/GPIO3/DIS_SPIS_113") (pintype "passive"))
      (node (ref "R30") (pin "2") (pinfunction "2_2") (pintype "passive"))
      (node (ref "R52") (pin "1") (pinfunction "1_1") (pintype "passive"))
    )
    (net (code "59") (name "/P5AN") (class "Default")
      (node (ref "DD1") (pin "49") (pinfunction "P5MDIAN_49") (pintype "passive"))
      (node (ref "XS6") (pin "10") (pinfunction "MD1-_10") (pintype "passive"))
    )
    (net (code "60") (name "/P5AP") (class "Default")
      (node (ref "DD1") (pin "48") (pinfunction "P5MDIAP_48") (pintype "passive"))
      (node (ref "XS6") (pin "11") (pinfunction "MD1+_11") (pintype "passive"))
    )
    (net (code "61") (name "/P5BN") (class "Default")
      (node (ref "DD1") (pin "51") (pinfunction "P5MDIBN_51") (pintype "passive"))
      (node (ref "XS6") (pin "5") (pinfunction "MD2-_5") (pintype "passive"))
    )
    (net (code "62") (name "/P5BP") (class "Default")
      (node (ref "DD1") (pin "50") (pinfunction "P5MDIBP_50") (pintype "passive"))
      (node (ref "XS6") (pin "4") (pinfunction "MD2+_4") (pintype "passive"))
    )
    (net (code "63") (name "/P5CN") (class "Default")
      (node (ref "DD1") (pin "54") (pinfunction "P5MDICN_54") (pintype "passive"))
      (node (ref "XS6") (pin "2") (pinfunction "MD3-_2") (pintype "passive"))
    )
    (net (code "64") (name "/P5CP") (class "Default")
      (node (ref "DD1") (pin "53") (pinfunction "P5MDICP_53") (pintype "passive"))
      (node (ref "XS6") (pin "3") (pinfunction "MD3+_3") (pintype "passive"))
    )
    (net (code "65") (name "/P5DN") (class "Default")
      (node (ref "DD1") (pin "56") (pinfunction "P5MDIDN_56") (pintype "passive"))
      (node (ref "XS6") (pin "9") (pinfunction "MD4-_9") (pintype "passive"))
    )
    (net (code "66") (name "/P5DP") (class "Default")
      (node (ref "DD1") (pin "55") (pinfunction "P5MDIDP_55") (pintype "passive"))
      (node (ref "XS6") (pin "8") (pinfunction "MD4+_8") (pintype "passive"))
    )
    (net (code "67") (name "/P5LED0") (class "Default")
      (node (ref "DD1") (pin "93") (pinfunction "RG2_RXD2/M2_RXD2/P2_TXD2/P5LED0/GPIO15_93") (pintype "passive"))
      (node (ref "R29") (pin "1") (pinfunction "1_1") (pintype "passive"))
      (node (ref "XS6") (pin "13") (pinfunction "LED_GRN-_13") (pintype "passive"))
    )
    (net (code "68") (name "/P5LED1") (class "Default")
      (node (ref "DD1") (pin "94") (pinfunction "RG2_RXD3/M2_RXD3/P2_TXD3/P5LED1/GPIO16_94") (pintype "passive"))
      (node (ref "R33") (pin "1") (pinfunction "1_1") (pintype "passive"))
      (node (ref "XS6") (pin "15") (pinfunction "LED_YELLOW+_15") (pintype "passive"))
    )
    (net (code "69") (name "/P5LED2") (class "Default")
      (node (ref "DD1") (pin "92") (pinfunction "RG2_RXD1/M2_RXD1/P2_TXD1/P5LED2/GPIO0_92") (pintype "passive"))
      (node (ref "R27") (pin "1") (pinfunction "1_1") (pintype "passive"))
      (node (ref "R54") (pin "1") (pinfunction "1_1") (pintype "passive"))
    )
    (net (code "70") (name "/P6AN") (class "Default")
      (node (ref "DD1") (pin "63") (pinfunction "P6MDIAN_63") (pintype "passive"))
      (node (ref "XS7") (pin "10") (pinfunction "MD1-_10") (pintype "passive"))
    )
    (net (code "71") (name "/P6AP") (class "Default")
      (node (ref "DD1") (pin "62") (pinfunction "P6MDIAP_62") (pintype "passive"))
      (node (ref "XS7") (pin "11") (pinfunction "MD1+_11") (pintype "passive"))
    )
    (net (code "72") (name "/P6BN") (class "Default")
      (node (ref "DD1") (pin "65") (pinfunction "P6MDIBN_65") (pintype "passive"))
      (node (ref "XS7") (pin "5") (pinfunction "MD2-_5") (pintype "passive"))
    )
    (net (code "73") (name "/P6BP") (class "Default")
      (node (ref "DD1") (pin "64") (pinfunction "P6MDIBP_64") (pintype "passive"))
      (node (ref "XS7") (pin "4") (pinfunction "MD2+_4") (pintype "passive"))
    )
    (net (code "74") (name "/P6CN") (class "Default")
      (node (ref "DD1") (pin "68") (pinfunction "P6MDICN_68") (pintype "passive"))
      (node (ref "XS7") (pin "2") (pinfunction "MD3-_2") (pintype "passive"))
    )
    (net (code "75") (name "/P6CP") (class "Default")
      (node (ref "DD1") (pin "67") (pinfunction "P6MDICP_67") (pintype "passive"))
      (node (ref "XS7") (pin "3") (pinfunction "MD3+_3") (pintype "passive"))
    )
    (net (code "76") (name "/P6DN") (class "Default")
      (node (ref "DD1") (pin "70") (pinfunction "P6MDIDN_70") (pintype "passive"))
      (node (ref "XS7") (pin "9") (pinfunction "MD4-_9") (pintype "passive"))
    )
    (net (code "77") (name "/P6DP") (class "Default")
      (node (ref "DD1") (pin "69") (pinfunction "P6MDIDP_69") (pintype "passive"))
      (node (ref "XS7") (pin "8") (pinfunction "MD4+_8") (pintype "passive"))
    )
    (net (code "78") (name "/P6LED0") (class "Default")
      (node (ref "DD1") (pin "90") (pinfunction "RG2_RXCTL/M2_RXDV/P2_TXEN/P6LED0/GPIO1/UARTRX_90") (pintype "passive"))
      (node (ref "R22") (pin "1") (pinfunction "1_1") (pintype "passive"))
      (node (ref "XS7") (pin "13") (pinfunction "LED_GRN-_13") (pintype "passive"))
    )
    (net (code "79") (name "/P6LED1") (class "Default")
      (node (ref "DD1") (pin "91") (pinfunction "RG2_RXD0/M2_RXD0/P2_TXD0/P6LED1/GPIO7/UARTTX_91") (pintype "passive"))
      (node (ref "R25") (pin "1") (pinfunction "1_1") (pintype "passive"))
      (node (ref "XS7") (pin "15") (pinfunction "LED_YELLOW+_15") (pintype "passive"))
    )
    (net (code "80") (name "/P6LED2") (class "Default")
      (node (ref "DD1") (pin "89") (pinfunction "RG2_RXC/M2_RXC/P2_TXC/P6LED2/GPIO14/SPF_CSn_89") (pintype "passive"))
      (node (ref "R20") (pin "1") (pinfunction "1_1") (pintype "passive"))
      (node (ref "R56") (pin "1") (pinfunction "1_1") (pintype "passive"))
    )
    (net (code "81") (name "/P7AN") (class "Default")
      (node (ref "DD1") (pin "73") (pinfunction "P7MDIAN_73") (pintype "passive"))
      (node (ref "XS8") (pin "10") (pinfunction "MD1-_10") (pintype "passive"))
    )
    (net (code "82") (name "/P7AP") (class "Default")
      (node (ref "DD1") (pin "72") (pinfunction "P7MDIAP_72") (pintype "passive"))
      (node (ref "XS8") (pin "11") (pinfunction "MD1+_11") (pintype "passive"))
    )
    (net (code "83") (name "/P7BN") (class "Default")
      (node (ref "DD1") (pin "75") (pinfunction "P7MDIBN_75") (pintype "passive"))
      (node (ref "XS8") (pin "5") (pinfunction "MD2-_5") (pintype "passive"))
    )
    (net (code "84") (name "/P7BP") (class "Default")
      (node (ref "DD1") (pin "74") (pinfunction "P7MDIBP_74") (pintype "passive"))
      (node (ref "XS8") (pin "4") (pinfunction "MD2+_4") (pintype "passive"))
    )
    (net (code "85") (name "/P7CN") (class "Default")
      (node (ref "DD1") (pin "78") (pinfunction "P7MDICN_78") (pintype "passive"))
      (node (ref "XS8") (pin "2") (pinfunction "MD3-_2") (pintype "passive"))
    )
    (net (code "86") (name "/P7CP") (class "Default")
      (node (ref "DD1") (pin "77") (pinfunction "P7MDICP_77") (pintype "passive"))
      (node (ref "XS8") (pin "3") (pinfunction "MD3+_3") (pintype "passive"))
    )
    (net (code "87") (name "/P7DN") (class "Default")
      (node (ref "DD1") (pin "80") (pinfunction "P7MDIDN_80") (pintype "passive"))
      (node (ref "XS8") (pin "9") (pinfunction "MD4-_9") (pintype "passive"))
    )
    (net (code "88") (name "/P7DP") (class "Default")
      (node (ref "DD1") (pin "79") (pinfunction "P7MDIDP_79") (pintype "passive"))
      (node (ref "XS8") (pin "8") (pinfunction "MD4+_8") (pintype "passive"))
    )
    (net (code "89") (name "/P7LED0") (class "Default")
      (node (ref "DD1") (pin "86") (pinfunction "RG2_TXD0/M2_TXD0/P2_RXD0/P7LED0/GPIO11/SPF_SI_D0_86") (pintype "passive"))
      (node (ref "R15") (pin "1") (pinfunction "1_1") (pintype "passive"))
      (node (ref "XS8") (pin "13") (pinfunction "LED_GRN-_13") (pintype "passive"))
    )
    (net (code "90") (name "/P7LED1") (class "Default")
      (node (ref "DD1") (pin "87") (pinfunction "RG2_TXCTL/M2_TXEN/P2_RXDV/P7LED1/GPIO12/SPF_SO_D1_87") (pintype "passive"))
      (node (ref "R18") (pin "1") (pinfunction "1_1") (pintype "passive"))
      (node (ref "XS8") (pin "15") (pinfunction "LED_YELLOW+_15") (pintype "passive"))
    )
    (net (code "91") (name "/P7LED2") (class "Default")
      (node (ref "DD1") (pin "85") (pinfunction "RG2_TXD1/M2_TXD1/P2_RXD1/P7LED2/GPIO10/SPF_CLK_85") (pintype "passive"))
      (node (ref "R13") (pin "1") (pinfunction "1_1") (pintype "passive"))
      (node (ref "R58") (pin "1") (pinfunction "1_1") (pintype "passive"))
    )
    (net (code "92") (name "AVDDH") (class "Default")
      (node (ref "C2") (pin "2") (pinfunction "2_2") (pintype "passive"))
      (node (ref "C9") (pin "1") (pinfunction "1_1") (pintype "passive"))
      (node (ref "DD1") (pin "138") (pinfunction "AVDDH_138") (pintype "passive"))
      (node (ref "DD1") (pin "148") (pinfunction "AVDDH_148") (pintype "passive"))
      (node (ref "DD1") (pin "15") (pinfunction "AVDDH_15") (pintype "passive"))
      (node (ref "DD1") (pin "158") (pinfunction "AVDDH_158") (pintype "passive"))
      (node (ref "DD1") (pin "162") (pinfunction "AVDDH_162") (pintype "passive"))
      (node (ref "DD1") (pin "172") (pinfunction "AVDDH_172") (pintype "passive"))
      (node (ref "DD1") (pin "37") (pinfunction "AVDDH_37") (pintype "passive"))
      (node (ref "DD1") (pin "47") (pinfunction "AVDDH_47") (pintype "passive"))
      (node (ref "DD1") (pin "57") (pinfunction "AVDDH_57") (pintype "passive"))
      (node (ref "DD1") (pin "6") (pinfunction "AVDDH_6") (pintype "passive"))
      (node (ref "DD1") (pin "61") (pinfunction "AVDDH_61") (pintype "passive"))
      (node (ref "DD1") (pin "71") (pinfunction "AVDDH_71") (pintype "passive"))
      (node (ref "DD1") (pin "81") (pinfunction "AVDDH_81") (pintype "passive"))
      (node (ref "DD1") (pin "97") (pinfunction "SVDDH_97") (pintype "passive"))
      (node (ref "FB1") (pin "1") (pinfunction "1_1") (pintype "passive"))
    )
    (net (code "93") (name "AVDDL") (class "Default")
      (node (ref "C13") (pin "1") (pinfunction "1_1") (pintype "passive"))
      (node (ref "C15") (pin "1") (pinfunction "1_1") (pintype "passive"))
      (node (ref "C17") (pin "1") (pinfunction "1_1") (pintype "passive"))
      (node (ref "C3") (pin "2") (pinfunction "2_2") (pintype "passive"))
      (node (ref "DD1") (pin "1") (pinfunction "AVDDL_1") (pintype "passive"))
      (node (ref "DD1") (pin "104") (pinfunction "SVDDL_104") (pintype "passive"))
      (node (ref "DD1") (pin "107") (pinfunction "SVDDL_107") (pintype "passive"))
      (node (ref "DD1") (pin "12") (pinfunction "AVDDL_12") (pintype "passive"))
      (node (ref "DD1") (pin "143") (pinfunction "AVDDL_143") (pintype "passive"))
      (node (ref "DD1") (pin "153") (pinfunction "AVDDL_153") (pintype "passive"))
      (node (ref "DD1") (pin "167") (pinfunction "AVDDL_167") (pintype "passive"))
      (node (ref "DD1") (pin "42") (pinfunction "AVDDL_42") (pintype "passive"))
      (node (ref "DD1") (pin "52") (pinfunction "AVDDL_52") (pintype "passive"))
      (node (ref "DD1") (pin "66") (pinfunction "AVDDL_66") (pintype "passive"))
      (node (ref "DD1") (pin "76") (pinfunction "AVDDL_76") (pintype "passive"))
      (node (ref "DD1") (pin "98") (pinfunction "SVDDL_98") (pintype "passive"))
      (node (ref "FB2") (pin "1") (pinfunction "1_1") (pintype "passive"))
    )
    (net (code "94") (name "GND") (class "Default")
      (node (ref "C1") (pin "1") (pinfunction "1_1") (pintype "passive"))
      (node (ref "C10") (pin "2") (pinfunction "2_2") (pintype "passive"))
      (node (ref "C11") (pin "2") (pinfunction "2_2") (pintype "passive"))
      (node (ref "C12") (pin "1") (pinfunction "1_1") (pintype "passive"))
      (node (ref "C13") (pin "2") (pinfunction "2_2") (pintype "passive"))
      (node (ref "C14") (pin "2") (pinfunction "2_2") (pintype "passive"))
      (node (ref "C15") (pin "2") (pinfunction "2_2") (pintype "passive"))
      (node (ref "C16") (pin "1") (pinfunction "1_1") (pintype "passive"))
      (node (ref "C17") (pin "2") (pinfunction "2_2") (pintype "passive"))
      (node (ref "C18") (pin "1") (pinfunction "1_1") (pintype "passive"))
      (node (ref "C19") (pin "1") (pinfunction "1_1") (pintype "passive"))
      (node (ref "C2") (pin "1") (pinfunction "1_1") (pintype "passive"))
      (node (ref "C22") (pin "1") (pinfunction "1_1") (pintype "passive"))
      (node (ref "C23") (pin "1") (pinfunction "1_1") (pintype "passive"))
      (node (ref "C24") (pin "1") (pinfunction "1_1") (pintype "passive"))
      (node (ref "C25") (pin "2") (pinfunction "2_2") (pintype "passive"))
      (node (ref "C26") (pin "2") (pinfunction "2_2") (pintype "passive"))
      (node (ref "C27") (pin "2") (pinfunction "2_2") (pintype "passive"))
      (node (ref "C28") (pin "2") (pinfunction "2_2") (pintype "passive"))
      (node (ref "C29") (pin "2") (pinfunction "2_2") (pintype "passive"))
      (node (ref "C3") (pin "1") (pinfunction "1_1") (pintype "passive"))
      (node (ref "C30") (pin "2") (pinfunction "2_2") (pintype "passive"))
      (node (ref "C31") (pin "2") (pinfunction "2_2") (pintype "passive"))
      (node (ref "C32") (pin "2") (pinfunction "2_2") (pintype "passive"))
      (node (ref "C4") (pin "1") (pinfunction "1_1") (pintype "passive"))
      (node (ref "C5") (pin "1") (pinfunction "1_1") (pintype "passive"))
      (node (ref "C8") (pin "2") (pinfunction "2_2") (pintype "passive"))
      (node (ref "C9") (pin "2") (pinfunction "2_2") (pintype "passive"))
      (node (ref "DA1") (pin "4") (pinfunction "GND_4") (pintype "passive"))
      (node (ref "DA2") (pin "4") (pinfunction "GND_4") (pintype "passive"))
      (node (ref "DD1") (pin "101") (pinfunction "SGND_101") (pintype "passive"))
      (node (ref "DD1") (pin "110") (pinfunction "SGND_110") (pintype "passive"))
      (node (ref "DD1") (pin "161") (pinfunction "PLLGND0_161") (pintype "passive"))
      (node (ref "DD1") (pin "177") (pinfunction "GND(EPAD)_177") (pintype "passive"))
      (node (ref "DD1") (pin "60") (pinfunction "PLLGND1_60") (pintype "passive"))
      (node (ref "DD1") (pin "8") (pinfunction "AGND_8") (pintype "passive"))
      (node (ref "R1") (pin "2") (pinfunction "2_2") (pintype "passive"))
      (node (ref "R11") (pin "2") (pinfunction "2_2") (pintype "passive"))
      (node (ref "R3") (pin "2") (pinfunction "2_2") (pintype "passive"))
      (node (ref "R32") (pin "1") (pinfunction "1_1") (pintype "passive"))
      (node (ref "R34") (pin "2") (pinfunction "2_2") (pintype "passive"))
      (node (ref "R35") (pin "1") (pinfunction "1_1") (pintype "passive"))
      (node (ref "R36") (pin "2") (pinfunction "2_2") (pintype "passive"))
      (node (ref "R38") (pin "2") (pinfunction "2_2") (pintype "passive"))
      (node (ref "R40") (pin "1") (pinfunction "1_1") (pintype "passive"))
      (node (ref "R42") (pin "2") (pinfunction "2_2") (pintype "passive"))
      (node (ref "R5") (pin "1") (pinfunction "1_1") (pintype "passive"))
      (node (ref "R8") (pin "2") (pinfunction "2_2") (pintype "passive"))
      (node (ref "S1") (pin "1") (pinfunction "1_1") (pintype "passive"))
      (node (ref "ZQ1") (pin "2") (pinfunction "GND_2") (pintype "passive"))
      (node (ref "ZQ1") (pin "4") (pinfunction "GND_4") (pintype "passive"))
    )
    (net (code "95") (name "GND_ETH") (class "Default")
      (node (ref "C4") (pin "2") (pinfunction "2_2") (pintype "passive"))
      (node (ref "R5") (pin "2") (pinfunction "2_2") (pintype "passive"))
      (node (ref "XS1") (pin "0") (pinfunction "Корпус_0") (pintype "passive"))
      (node (ref "XS2") (pin "0") (pinfunction "Корпус_0") (pintype "passive"))
      (node (ref "XS3") (pin "0") (pinfunction "Корпус_0") (pintype "passive"))
      (node (ref "XS4") (pin "0") (pinfunction "Корпус_0") (pintype "passive"))
      (node (ref "XS5") (pin "0") (pinfunction "Корпус_0") (pintype "passive"))
      (node (ref "XS6") (pin "0") (pinfunction "Корпус_0") (pintype "passive"))
      (node (ref "XS7") (pin "0") (pinfunction "Корпус_0") (pintype "passive"))
      (node (ref "XS8") (pin "0") (pinfunction "Корпус_0") (pintype "passive"))
    )
    (net (code "96") (name "Net-(DA1-BST)") (class "Default")
      (node (ref "C6") (pin "1") (pinfunction "1_1") (pintype "passive"))
      (node (ref "DA1") (pin "6") (pinfunction "BST_6") (pintype "passive"))
    )
    (net (code "97") (name "Net-(DA1-FB)") (class "Default")
      (node (ref "C7") (pin "1") (pinfunction "1_1") (pintype "passive"))
      (node (ref "DA1") (pin "1") (pinfunction "FB_1") (pintype "passive"))
      (node (ref "R31") (pin "1") (pinfunction "1_1") (pintype "passive"))
      (node (ref "R32") (pin "2") (pinfunction "2_2") (pintype "passive"))
    )
    (net (code "98") (name "Net-(DA1-SW)") (class "Default")
      (node (ref "C6") (pin "2") (pinfunction "2_2") (pintype "passive"))
      (node (ref "DA1") (pin "5") (pinfunction "SW_5") (pintype "passive"))
      (node (ref "L1") (pin "1") (pinfunction "1_1") (pintype "passive"))
    )
    (net (code "99") (name "Net-(DA2-BST)") (class "Default")
      (node (ref "C20") (pin "1") (pinfunction "1_1") (pintype "passive"))
      (node (ref "DA2") (pin "6") (pinfunction "BST_6") (pintype "passive"))
    )
    (net (code "100") (name "Net-(DA2-FB)") (class "Default")
      (node (ref "C21") (pin "1") (pinfunction "1_1") (pintype "passive"))
      (node (ref "DA2") (pin "1") (pinfunction "FB_1") (pintype "passive"))
      (node (ref "R39") (pin "1") (pinfunction "1_1") (pintype "passive"))
      (node (ref "R40") (pin "2") (pinfunction "2_2") (pintype "passive"))
    )
    (net (code "101") (name "Net-(DA2-SW)") (class "Default")
      (node (ref "C20") (pin "2") (pinfunction "2_2") (pintype "passive"))
      (node (ref "DA2") (pin "5") (pinfunction "SW_5") (pintype "passive"))
      (node (ref "L2") (pin "1") (pinfunction "1_1") (pintype "passive"))
    )
    (net (code "102") (name "Net-(DD1-BUZZER{slash}DIS_LPD)") (class "Default")
      (node (ref "DD1") (pin "20") (pinfunction "BUZZER/DIS_LPD_20") (pintype "passive"))
      (node (ref "R37") (pin "2") (pinfunction "2_2") (pintype "passive"))
    )
    (net (code "103") (name "Net-(DD1-GPIO_A{slash}SPF_MUX_SEL)") (class "Default")
      (node (ref "DD1") (pin "24") (pinfunction "GPIO_A/SPF_MUX_SEL_24") (pintype "passive"))
      (node (ref "R42") (pin "1") (pinfunction "1_1") (pintype "passive"))
    )
    (net (code "104") (name "Net-(DD1-MDIREF)") (class "Default")
      (node (ref "DD1") (pin "10") (pinfunction "MDIREF_10") (pintype "passive"))
      (node (ref "R35") (pin "2") (pinfunction "2_2") (pintype "passive"))
    )
    (net (code "105") (name "Net-(DD1-P8LED2{slash}DIS_FX_AUTO)") (class "Default")
      (node (ref "DD1") (pin "29") (pinfunction "P8LED2/DIS_FX_AUTO_29") (pintype "passive"))
      (node (ref "R6") (pin "1") (pinfunction "1_1") (pintype "passive"))
    )
    (net (code "106") (name "Net-(DD1-P9LED0{slash}EN_PWRLIGHT)") (class "Default")
      (node (ref "DD1") (pin "26") (pinfunction "P9LED0/EN_PWRLIGHT_26") (pintype "passive"))
      (node (ref "R1") (pin "1") (pinfunction "1_1") (pintype "passive"))
    )
    (net (code "107") (name "Net-(DD1-P9LED1{slash}DISAUTOLOAD)") (class "Default")
      (node (ref "DD1") (pin "27") (pinfunction "P9LED1/DISAUTOLOAD_27") (pintype "passive"))
      (node (ref "R2") (pin "1") (pinfunction "1_1") (pintype "passive"))
    )
    (net (code "108") (name "Net-(DD1-P9LED2{slash}EEE_EN)") (class "Default")
      (node (ref "DD1") (pin "28") (pinfunction "P9LED2/EEE_EN_28") (pintype "passive"))
      (node (ref "R3") (pin "1") (pinfunction "1_1") (pintype "passive"))
    )
    (net (code "109") (name "Net-(DD1-RESERVED1)") (class "Default")
      (node (ref "DD1") (pin "21") (pinfunction "RESERVED1_21") (pintype "passive"))
      (node (ref "R38") (pin "1") (pinfunction "1_1") (pintype "passive"))
    )
    (net (code "110") (name "Net-(DD1-RESERVED2)") (class "Default")
      (node (ref "DD1") (pin "22") (pinfunction "RESERVED2_22") (pintype "passive"))
      (node (ref "R36") (pin "1") (pinfunction "1_1") (pintype "passive"))
    )
    (net (code "111") (name "Net-(DD1-RESERVED3)") (class "Default")
      (node (ref "DD1") (pin "23") (pinfunction "RESERVED3_23") (pintype "passive"))
      (node (ref "R34") (pin "1") (pinfunction "1_1") (pintype "passive"))
    )
    (net (code "112") (name "Net-(DD1-RG2_TXD2{slash}M2_TXD2{slash}P2_RXD2{slash}P8LED0{slash}GPIO9{slash}EN_FLASH)") (class "Default")
      (node (ref "DD1") (pin "84") (pinfunction "RG2_TXD2/M2_TXD2/P2_RXD2/P8LED0/GPIO9/EN_FLASH_84") (pintype "passive"))
      (node (ref "R11") (pin "1") (pinfunction "1_1") (pintype "passive"))
    )
    (net (code "113") (name "Net-(DD1-RG2_TXD3{slash}M2_TXD3{slash}P2_RXD3{slash}P8LED1{slash}GPIO8{slash}DIS_LED)") (class "Default")
      (node (ref "DD1") (pin "83") (pinfunction "RG2_TXD3/M2_TXD3/P2_RXD3/P8LED1/GPIO8/DIS_LED_83") (pintype "passive"))
      (node (ref "R8") (pin "1") (pinfunction "1_1") (pintype "passive"))
    )
    (net (code "114") (name "Net-(DD1-Slave_SPI_SO{slash}EEPROM_MOD)") (class "Default")
      (node (ref "DD1") (pin "137") (pinfunction "Slave_SPI_SO/EEPROM_MOD_137") (pintype "passive"))
      (node (ref "R41") (pin "1") (pinfunction "1_1") (pintype "passive"))
    )
    (net (code "115") (name "Net-(DD1-XTALI)") (class "Default")
      (node (ref "C8") (pin "1") (pinfunction "1_1") (pintype "passive"))
      (node (ref "DD1") (pin "132") (pinfunction "XTALI_132") (pintype "passive"))
      (node (ref "ZQ1") (pin "1") (pinfunction "1_1") (pintype "passive"))
    )
    (net (code "116") (name "Net-(DD1-XTALO)") (class "Default")
      (node (ref "C11") (pin "1") (pinfunction "1_1") (pintype "passive"))
      (node (ref "DD1") (pin "131") (pinfunction "XTALO_131") (pintype "passive"))
      (node (ref "ZQ1") (pin "3") (pinfunction "3_3") (pintype "passive"))
    )
    (net (code "117") (name "Net-(DD1-nRESET)") (class "Default")
      (node (ref "DD1") (pin "133") (pinfunction "nRESET_133") (pintype "passive"))
      (node (ref "S1") (pin "2") (pinfunction "2_2") (pintype "passive"))
    )
    (net (code "118") (name "Net-(XS1-LED_GRN+)") (class "Default")
      (node (ref "R45") (pin "2") (pinfunction "2_2") (pintype "passive"))
      (node (ref "XS1") (pin "14") (pinfunction "LED_GRN+_14") (pintype "passive"))
    )
    (net (code "119") (name "Net-(XS1-LED_YELLOW-)") (class "Default")
      (node (ref "R44") (pin "2") (pinfunction "2_2") (pintype "passive"))
      (node (ref "XS1") (pin "16") (pinfunction "LED_YELLOW-_16") (pintype "passive"))
    )
    (net (code "120") (name "Net-(XS1-MDCT1)") (class "Default")
      (node (ref "C25") (pin "1") (pinfunction "1_1") (pintype "passive"))
      (node (ref "XS1") (pin "1") (pinfunction "MDCT3_1") (pintype "passive"))
      (node (ref "XS1") (pin "12") (pinfunction "MDCT1_12") (pintype "passive"))
      (node (ref "XS1") (pin "6") (pinfunction "MDCT2_6") (pintype "passive"))
      (node (ref "XS1") (pin "7") (pinfunction "MDCT4_7") (pintype "passive"))
    )
    (net (code "121") (name "Net-(XS2-LED_GRN+)") (class "Default")
      (node (ref "R46") (pin "2") (pinfunction "2_2") (pintype "passive"))
      (node (ref "XS2") (pin "14") (pinfunction "LED_GRN+_14") (pintype "passive"))
    )
    (net (code "122") (name "Net-(XS2-LED_YELLOW-)") (class "Default")
      (node (ref "R47") (pin "2") (pinfunction "2_2") (pintype "passive"))
      (node (ref "XS2") (pin "16") (pinfunction "LED_YELLOW-_16") (pintype "passive"))
    )
    (net (code "123") (name "Net-(XS2-MDCT1)") (class "Default")
      (node (ref "C26") (pin "1") (pinfunction "1_1") (pintype "passive"))
      (node (ref "XS2") (pin "1") (pinfunction "MDCT3_1") (pintype "passive"))
      (node (ref "XS2") (pin "12") (pinfunction "MDCT1_12") (pintype "passive"))
      (node (ref "XS2") (pin "6") (pinfunction "MDCT2_6") (pintype "passive"))
      (node (ref "XS2") (pin "7") (pinfunction "MDCT4_7") (pintype "passive"))
    )
    (net (code "124") (name "Net-(XS3-LED_GRN+)") (class "Default")
      (node (ref "R48") (pin "2") (pinfunction "2_2") (pintype "passive"))
      (node (ref "XS3") (pin "14") (pinfunction "LED_GRN+_14") (pintype "passive"))
    )
    (net (code "125") (name "Net-(XS3-LED_YELLOW-)") (class "Default")
      (node (ref "R49") (pin "2") (pinfunction "2_2") (pintype "passive"))
      (node (ref "XS3") (pin "16") (pinfunction "LED_YELLOW-_16") (pintype "passive"))
    )
    (net (code "126") (name "Net-(XS3-MDCT1)") (class "Default")
      (node (ref "C27") (pin "1") (pinfunction "1_1") (pintype "passive"))
      (node (ref "XS3") (pin "1") (pinfunction "MDCT3_1") (pintype "passive"))
      (node (ref "XS3") (pin "12") (pinfunction "MDCT1_12") (pintype "passive"))
      (node (ref "XS3") (pin "6") (pinfunction "MDCT2_6") (pintype "passive"))
      (node (ref "XS3") (pin "7") (pinfunction "MDCT4_7") (pintype "passive"))
    )
    (net (code "127") (name "Net-(XS4-LED_GRN+)") (class "Default")
      (node (ref "R43") (pin "2") (pinfunction "2_2") (pintype "passive"))
      (node (ref "XS4") (pin "14") (pinfunction "LED_GRN+_14") (pintype "passive"))
    )
    (net (code "128") (name "Net-(XS4-LED_YELLOW-)") (class "Default")
      (node (ref "R50") (pin "2") (pinfunction "2_2") (pintype "passive"))
      (node (ref "XS4") (pin "16") (pinfunction "LED_YELLOW-_16") (pintype "passive"))
    )
    (net (code "129") (name "Net-(XS4-MDCT1)") (class "Default")
      (node (ref "C28") (pin "1") (pinfunction "1_1") (pintype "passive"))
      (node (ref "XS4") (pin "1") (pinfunction "MDCT3_1") (pintype "passive"))
      (node (ref "XS4") (pin "12") (pinfunction "MDCT1_12") (pintype "passive"))
      (node (ref "XS4") (pin "6") (pinfunction "MDCT2_6") (pintype "passive"))
      (node (ref "XS4") (pin "7") (pinfunction "MDCT4_7") (pintype "passive"))
    )
    (net (code "130") (name "Net-(XS5-LED_GRN+)") (class "Default")
      (node (ref "R51") (pin "2") (pinfunction "2_2") (pintype "passive"))
      (node (ref "XS5") (pin "14") (pinfunction "LED_GRN+_14") (pintype "passive"))
    )
    (net (code "131") (name "Net-(XS5-LED_YELLOW-)") (class "Default")
      (node (ref "R52") (pin "2") (pinfunction "2_2") (pintype "passive"))
      (node (ref "XS5") (pin "16") (pinfunction "LED_YELLOW-_16") (pintype "passive"))
    )
    (net (code "132") (name "Net-(XS5-MDCT1)") (class "Default")
      (node (ref "C29") (pin "1") (pinfunction "1_1") (pintype "passive"))
      (node (ref "XS5") (pin "1") (pinfunction "MDCT3_1") (pintype "passive"))
      (node (ref "XS5") (pin "12") (pinfunction "MDCT1_12") (pintype "passive"))
      (node (ref "XS5") (pin "6") (pinfunction "MDCT2_6") (pintype "passive"))
      (node (ref "XS5") (pin "7") (pinfunction "MDCT4_7") (pintype "passive"))
    )
    (net (code "133") (name "Net-(XS6-LED_GRN+)") (class "Default")
      (node (ref "R53") (pin "2") (pinfunction "2_2") (pintype "passive"))
      (node (ref "XS6") (pin "14") (pinfunction "LED_GRN+_14") (pintype "passive"))
    )
    (net (code "134") (name "Net-(XS6-LED_YELLOW-)") (class "Default")
      (node (ref "R54") (pin "2") (pinfunction "2_2") (pintype "passive"))
      (node (ref "XS6") (pin "16") (pinfunction "LED_YELLOW-_16") (pintype "passive"))
    )
    (net (code "135") (name "Net-(XS6-MDCT1)") (class "Default")
      (node (ref "C30") (pin "1") (pinfunction "1_1") (pintype "passive"))
      (node (ref "XS6") (pin "1") (pinfunction "MDCT3_1") (pintype "passive"))
      (node (ref "XS6") (pin "12") (pinfunction "MDCT1_12") (pintype "passive"))
      (node (ref "XS6") (pin "6") (pinfunction "MDCT2_6") (pintype "passive"))
      (node (ref "XS6") (pin "7") (pinfunction "MDCT4_7") (pintype "passive"))
    )
    (net (code "136") (name "Net-(XS7-LED_GRN+)") (class "Default")
      (node (ref "R55") (pin "2") (pinfunction "2_2") (pintype "passive"))
      (node (ref "XS7") (pin "14") (pinfunction "LED_GRN+_14") (pintype "passive"))
    )
    (net (code "137") (name "Net-(XS7-LED_YELLOW-)") (class "Default")
      (node (ref "R56") (pin "2") (pinfunction "2_2") (pintype "passive"))
      (node (ref "XS7") (pin "16") (pinfunction "LED_YELLOW-_16") (pintype "passive"))
    )
    (net (code "138") (name "Net-(XS7-MDCT1)") (class "Default")
      (node (ref "C31") (pin "1") (pinfunction "1_1") (pintype "passive"))
      (node (ref "XS7") (pin "1") (pinfunction "MDCT3_1") (pintype "passive"))
      (node (ref "XS7") (pin "12") (pinfunction "MDCT1_12") (pintype "passive"))
      (node (ref "XS7") (pin "6") (pinfunction "MDCT2_6") (pintype "passive"))
      (node (ref "XS7") (pin "7") (pinfunction "MDCT4_7") (pintype "passive"))
    )
    (net (code "139") (name "Net-(XS8-LED_GRN+)") (class "Default")
      (node (ref "R57") (pin "2") (pinfunction "2_2") (pintype "passive"))
      (node (ref "XS8") (pin "14") (pinfunction "LED_GRN+_14") (pintype "passive"))
    )
    (net (code "140") (name "Net-(XS8-LED_YELLOW-)") (class "Default")
      (node (ref "R58") (pin "2") (pinfunction "2_2") (pintype "passive"))
      (node (ref "XS8") (pin "16") (pinfunction "LED_YELLOW-_16") (pintype "passive"))
    )
    (net (code "141") (name "Net-(XS8-MDCT1)") (class "Default")
      (node (ref "C32") (pin "1") (pinfunction "1_1") (pintype "passive"))
      (node (ref "XS8") (pin "1") (pinfunction "MDCT3_1") (pintype "passive"))
      (node (ref "XS8") (pin "12") (pinfunction "MDCT1_12") (pintype "passive"))
      (node (ref "XS8") (pin "6") (pinfunction "MDCT2_6") (pintype "passive"))
      (node (ref "XS8") (pin "7") (pinfunction "MDCT4_7") (pintype "passive"))
    )
    (net (code "142") (name "PLLVDDL0") (class "Default")
      (node (ref "C10") (pin "1") (pinfunction "1_1") (pintype "passive"))
      (node (ref "C14") (pin "1") (pinfunction "1_1") (pintype "passive"))
      (node (ref "C5") (pin "2") (pinfunction "2_2") (pintype "passive"))
      (node (ref "DD1") (pin "159") (pinfunction "PLLVDDL0_159") (pintype "passive"))
      (node (ref "DD1") (pin "58") (pinfunction "PLLVDDL1_58") (pintype "passive"))
      (node (ref "FB3") (pin "2") (pinfunction "2_2") (pintype "passive"))
    )
    (net (code "143") (name "unconnected-(DD1-ATESTCK0-Pad160)") (class "Default")
      (node (ref "DD1") (pin "160") (pinfunction "ATESTCK0_160") (pintype "passive+no_connect"))
    )
    (net (code "144") (name "unconnected-(DD1-ATESTCK1-Pad59)") (class "Default")
      (node (ref "DD1") (pin "59") (pinfunction "ATESTCK1_59") (pintype "passive+no_connect"))
    )
    (net (code "145") (name "unconnected-(DD1-GPIO_B{slash}SPF_CLK-Pad30)") (class "Default")
      (node (ref "DD1") (pin "30") (pinfunction "GPIO_B/SPF_CLK_30") (pintype "passive+no_connect"))
    )
    (net (code "146") (name "unconnected-(DD1-GPIO_C{slash}SPF_SI_D0-Pad31)") (class "Default")
      (node (ref "DD1") (pin "31") (pinfunction "GPIO_C/SPF_SI_D0_31") (pintype "passive+no_connect"))
    )
    (net (code "147") (name "unconnected-(DD1-GPIO_D{slash}SPF_SO_D1-Pad32)") (class "Default")
      (node (ref "DD1") (pin "32") (pinfunction "GPIO_D/SPF_SO_D1_32") (pintype "passive+no_connect"))
    )
    (net (code "148") (name "unconnected-(DD1-GPIO_E{slash}SPF_CSn-Pad33)") (class "Default")
      (node (ref "DD1") (pin "33") (pinfunction "GPIO_E/SPF_CSn_33") (pintype "passive+no_connect"))
    )
    (net (code "149") (name "unconnected-(DD1-INT-Pad19)") (class "Default")
      (node (ref "DD1") (pin "19") (pinfunction "INT_19") (pintype "passive+no_connect"))
    )
    (net (code "150") (name "unconnected-(DD1-NC-Pad7)") (class "Default")
      (node (ref "DD1") (pin "7") (pinfunction "NC_7") (pintype "passive+no_connect"))
    )
    (net (code "151") (name "unconnected-(DD1-NC-Pad9)") (class "Default")
      (node (ref "DD1") (pin "9") (pinfunction "NC_9") (pintype "passive+no_connect"))
    )
    (net (code "152") (name "unconnected-(DD1-NC-Pad11)") (class "Default")
      (node (ref "DD1") (pin "11") (pinfunction "NC_11") (pintype "passive+no_connect"))
    )
    (net (code "153") (name "unconnected-(DD1-RESERVED4-Pad25)") (class "Default")
      (node (ref "DD1") (pin "25") (pinfunction "RESERVED4_25") (pintype "passive+no_connect"))
    )
    (net (code "154") (name "unconnected-(DD1-RG2_TXC{slash}M2_TXC{slash}P2_RXC{slash}GPIO13-Pad88)") (class "Default")
      (node (ref "DD1") (pin "88") (pinfunction "RG2_TXC/M2_TXC/P2_RXC/GPIO13_88") (pintype "passive+no_connect"))
    )
    (net (code "155") (name "unconnected-(DD1-RTT1-Pad13)") (class "Default")
      (node (ref "DD1") (pin "13") (pinfunction "RTT1_13") (pintype "passive+no_connect"))
    )
    (net (code "156") (name "unconnected-(DD1-RTT2-Pad14)") (class "Default")
      (node (ref "DD1") (pin "14") (pinfunction "RTT2_14") (pintype "passive+no_connect"))
    )
    (net (code "157") (name "unconnected-(DD1-S0RXN-Pad108)") (class "Default")
      (node (ref "DD1") (pin "108") (pinfunction "S0RXN_108") (pintype "passive+no_connect"))
    )
    (net (code "158") (name "unconnected-(DD1-S0RXP-Pad109)") (class "Default")
      (node (ref "DD1") (pin "109") (pinfunction "S0RXP_109") (pintype "passive+no_connect"))
    )
    (net (code "159") (name "unconnected-(DD1-S0TXN-Pad105)") (class "Default")
      (node (ref "DD1") (pin "105") (pinfunction "S0TXN_105") (pintype "passive+no_connect"))
    )
    (net (code "160") (name "unconnected-(DD1-S0TXP-Pad106)") (class "Default")
      (node (ref "DD1") (pin "106") (pinfunction "S0TXP_106") (pintype "passive+no_connect"))
    )
    (net (code "161") (name "unconnected-(DD1-S1RXN-Pad103)") (class "Default")
      (node (ref "DD1") (pin "103") (pinfunction "S1RXN_103") (pintype "passive+no_connect"))
    )
    (net (code "162") (name "unconnected-(DD1-S1RXP-Pad102)") (class "Default")
      (node (ref "DD1") (pin "102") (pinfunction "S1RXP_102") (pintype "passive+no_connect"))
    )
    (net (code "163") (name "unconnected-(DD1-S1TXN-Pad100)") (class "Default")
      (node (ref "DD1") (pin "100") (pinfunction "S1TXN_100") (pintype "passive+no_connect"))
    )
    (net (code "164") (name "unconnected-(DD1-S1TXP-Pad99)") (class "Default")
      (node (ref "DD1") (pin "99") (pinfunction "S1TXP_99") (pintype "passive+no_connect"))
    )
    (net (code "165") (name "unconnected-(DD1-SCK{slash}MMD_MDC{slash}Slave_SPI_SCK-Pad135)") (class "Default")
      (node (ref "DD1") (pin "135") (pinfunction "SCK/MMD_MDC/Slave_SPI_SCK_135") (pintype "passive+no_connect"))
    )
    (net (code "166") (name "unconnected-(DD1-SDA{slash}MMD_MDIO{slash}Slave_SPI_SI-Pad136)") (class "Default")
      (node (ref "DD1") (pin "136") (pinfunction "SDA/MMD_MDIO/Slave_SPI_SI_136") (pintype "passive+no_connect"))
    )
    (net (code "167") (name "unconnected-(DD1-Slave_SPI_SS#-Pad134)") (class "Default")
      (node (ref "DD1") (pin "134") (pinfunction "Slave_SPI_SS#_134") (pintype "passive+no_connect"))
    )
    (net (code "168") (name "unconnected-(XS3-LED_GRN--Pad13)") (class "Default")
      (node (ref "XS3") (pin "13") (pinfunction "LED_GRN-_13") (pintype "passive"))
    )
  )
)
